# NC.net
KiCad netlist of a schematic drawn in Altium Designer
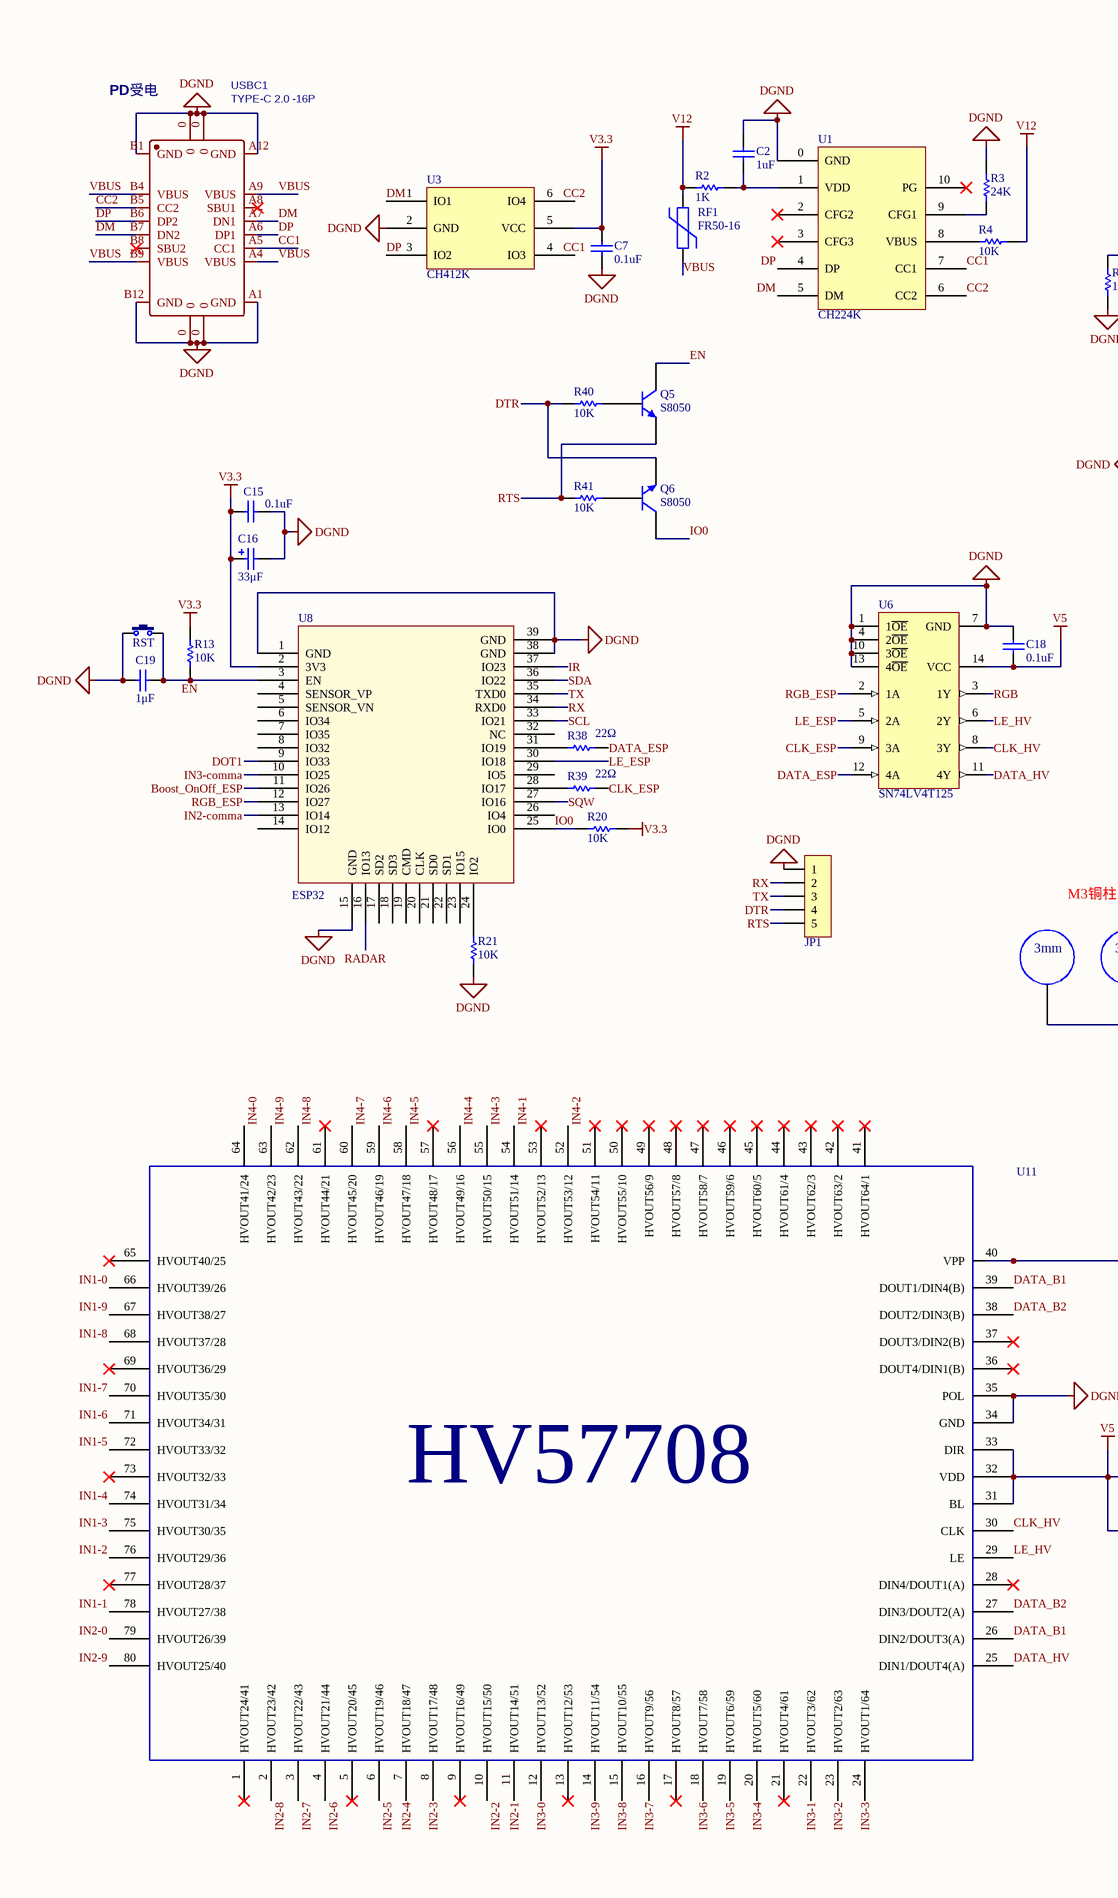
[diagram p0: NC.SchDoc, left]
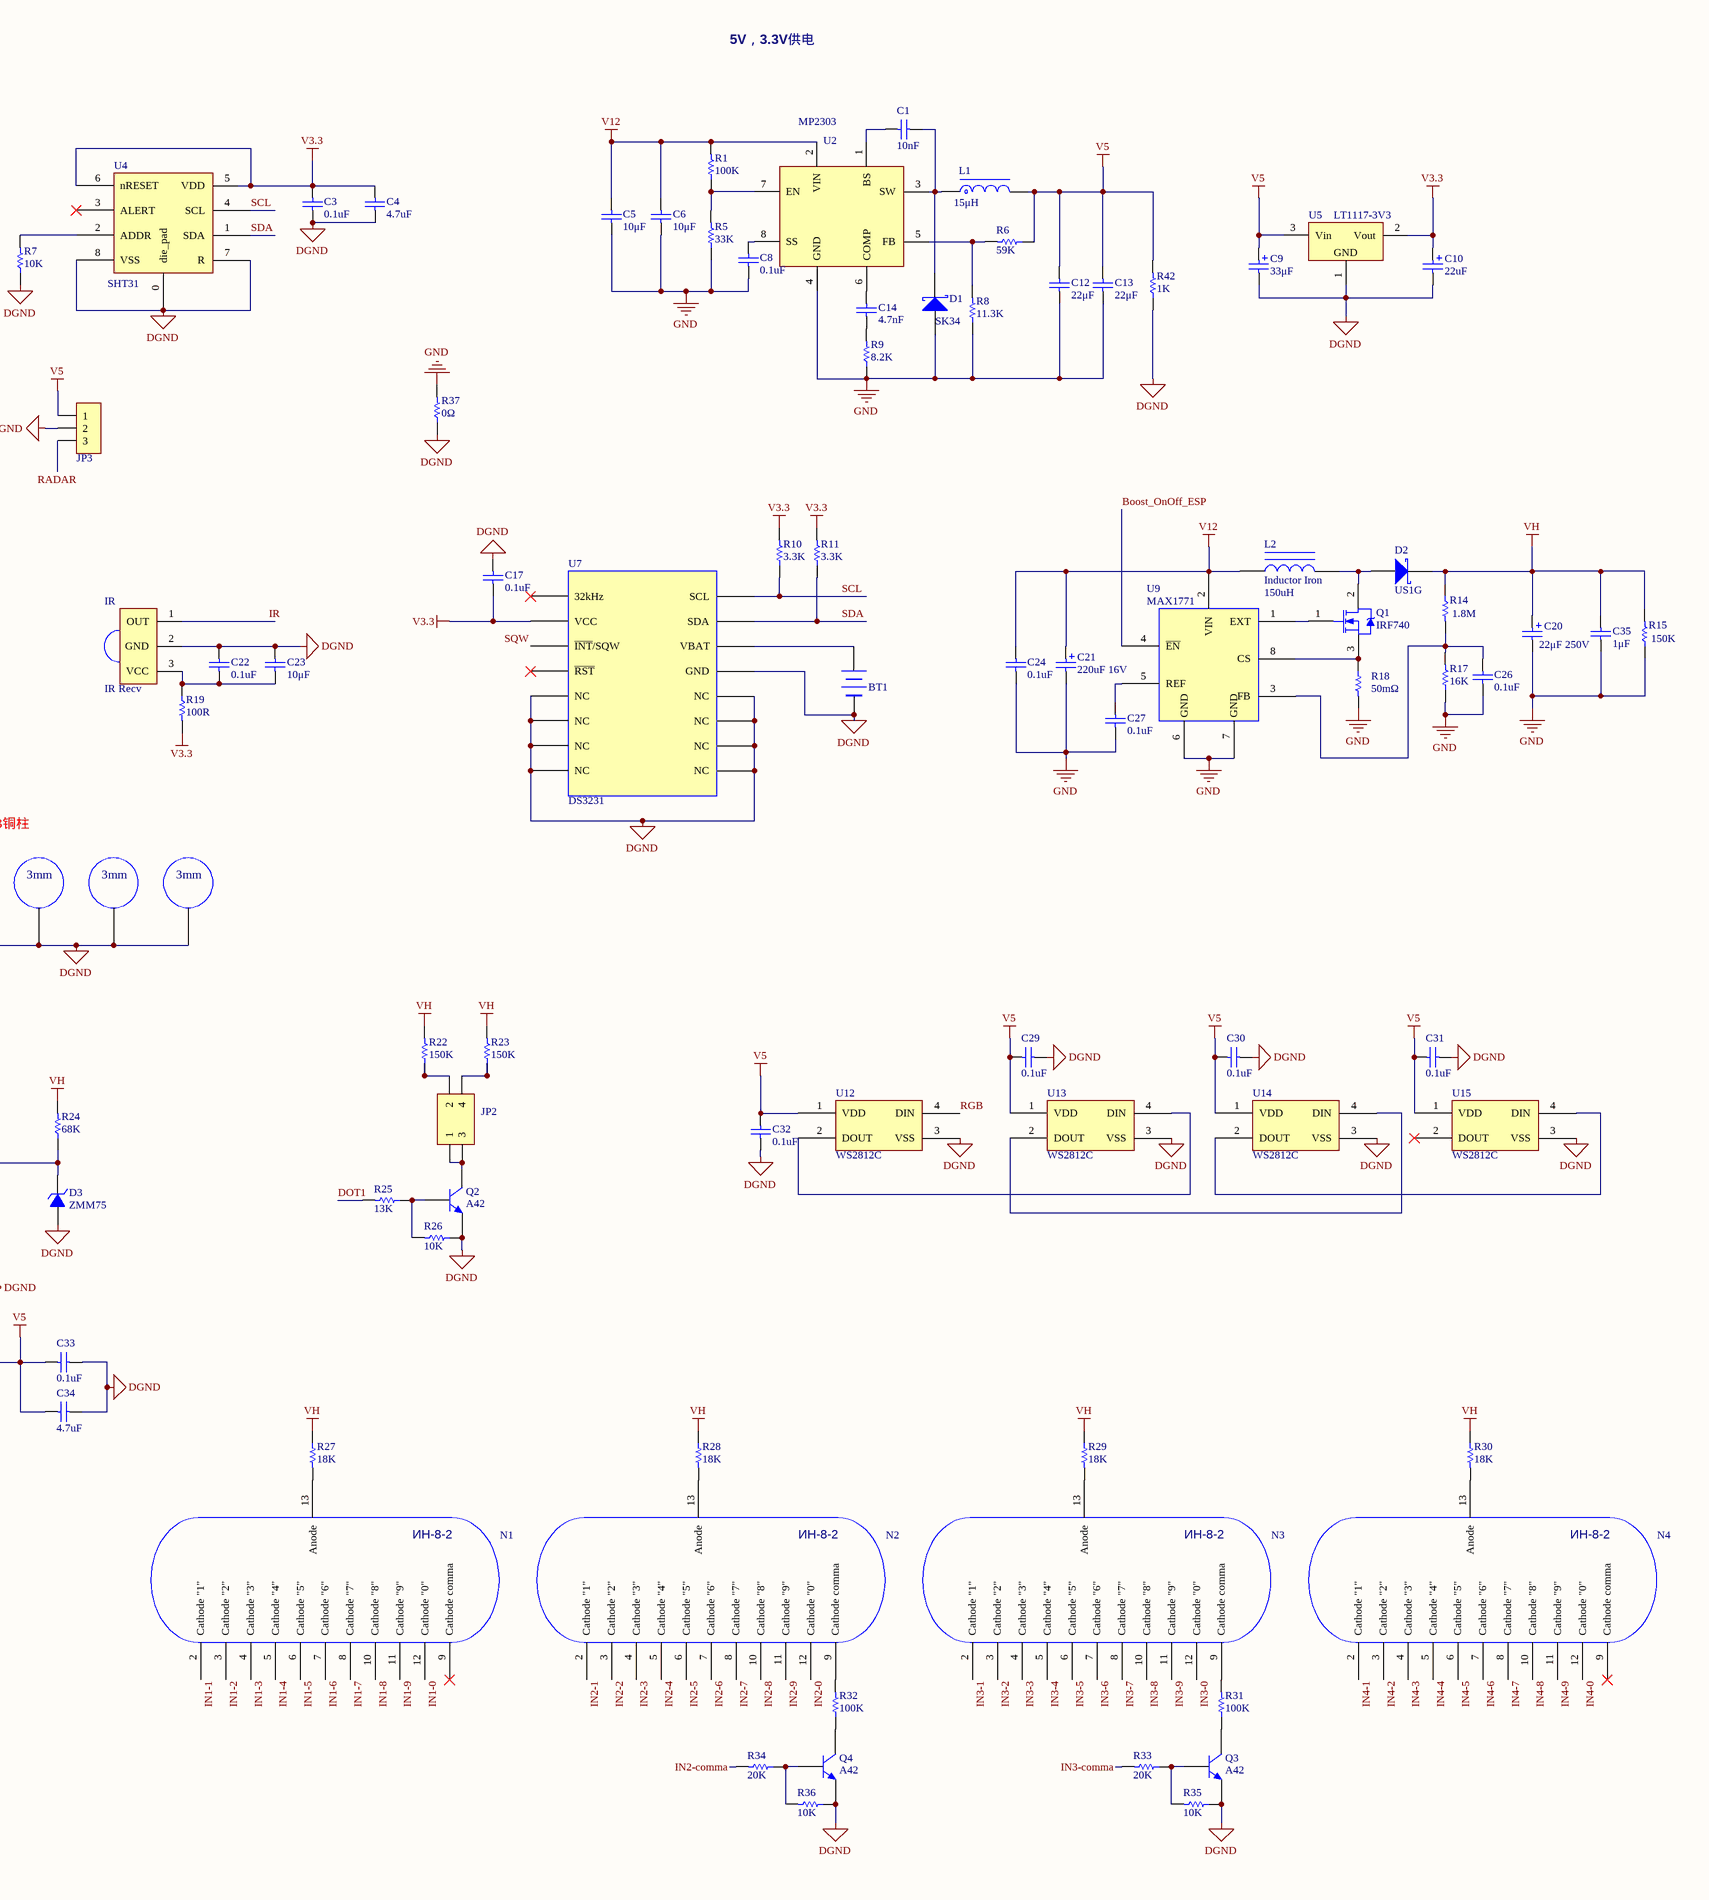
[diagram p1: NC.SchDoc, right]

(export (version "E")
  (design (tool "Eeschema 10.0.6"))
  (components
    (comp (ref "BT1")
      (value "CR1220 holder")
      (footprint "BAT1220")
      (libsource (lib "Schlib1") (part "BATTERY"))
    )
    (comp (ref "C1")
      (value "10nF")
      (footprint "C 0805_L")
      (description "Capacitor")
      (fields (field (name "Comment") "Cap") (field (name "PUBLISHER") "Altium Limited"))
      (libsource (lib "Nixie") (part "Cap"))
    )
    (comp (ref "C2")
      (value "1uF")
      (footprint "C 0805_L")
      (description "Capacitor")
      (fields (field (name "Comment") "Cap") (field (name "PUBLISHER") "Altium Limited"))
      (libsource (lib "Nixie") (part "Cap"))
    )
    (comp (ref "C3")
      (value "0.1uF")
      (footprint "C 0805_L")
      (description "Capacitor")
      (fields (field (name "Comment") "Cap") (field (name "PUBLISHER") "Altium Limited"))
      (libsource (lib "Schlib1") (part "Cap"))
    )
    (comp (ref "C4")
      (value "4.7uF")
      (footprint "C 0805_L")
      (description "Capacitor")
      (fields (field (name "Comment") "Cap") (field (name "PUBLISHER") "Altium Limited"))
      (libsource (lib "Schlib1") (part "Cap"))
    )
    (comp (ref "C5")
      (value "10μF")
      (footprint "C 0805_L")
      (description "Capacitor")
      (fields (field (name "Comment") "Cap") (field (name "PUBLISHER") "Altium Limited"))
      (libsource (lib "Nixie") (part "Cap"))
    )
    (comp (ref "C6")
      (value "10μF")
      (footprint "C 0805_L")
      (description "Capacitor")
      (fields (field (name "Comment") "Cap") (field (name "PUBLISHER") "Altium Limited"))
      (libsource (lib "Nixie") (part "Cap"))
    )
    (comp (ref "C7")
      (value "0.1uF")
      (footprint "C 0805_L")
      (description "Capacitor")
      (fields (field (name "Comment") "Cap") (field (name "PUBLISHER") "Altium Limited"))
      (libsource (lib "Schlib1") (part "Cap"))
    )
    (comp (ref "C8")
      (value "0.1uF")
      (footprint "C 0805_L")
      (description "Capacitor")
      (fields (field (name "Comment") "Cap") (field (name "PUBLISHER") "Altium Limited"))
      (libsource (lib "Nixie") (part "Cap"))
    )
    (comp (ref "C9")
      (value "33μF")
      (footprint "CM C(5*5.4)")
      (description "Polarized Capacitor (Radial)")
      (fields (field (name "Comment") "Cap Pol1") (field (name "PUBLISHER") "Altium Limited"))
      (libsource (lib "Nixie") (part "Cap Pol1"))
    )
    (comp (ref "C10")
      (value "22uF")
      (footprint "CD C(6032)")
      (description "Polarized Capacitor (Radial)")
      (fields (field (name "Comment") "Cap Pol1") (field (name "PUBLISHER") "Altium Limited"))
      (libsource (lib "Nixie") (part "Cap Pol1"))
    )
    (comp (ref "C12")
      (value "22μF")
      (footprint "C 1206_L")
      (description "Capacitor")
      (fields (field (name "Comment") "Cap") (field (name "PUBLISHER") "Altium Limited"))
      (libsource (lib "Nixie") (part "Cap"))
    )
    (comp (ref "C13")
      (value "22μF")
      (footprint "C 1206_L")
      (description "Capacitor")
      (fields (field (name "Comment") "Cap") (field (name "PUBLISHER") "Altium Limited"))
      (libsource (lib "Nixie") (part "Cap"))
    )
    (comp (ref "C14")
      (value "4.7nF")
      (footprint "C 0805_L")
      (description "Capacitor")
      (fields (field (name "Comment") "Cap") (field (name "PUBLISHER") "Altium Limited"))
      (libsource (lib "Nixie") (part "Cap"))
    )
    (comp (ref "C15")
      (value "0.1uF")
      (footprint "C 0805_L")
      (description "Capacitor")
      (fields (field (name "Comment") "Cap") (field (name "PUBLISHER") "Altium Limited"))
      (libsource (lib "Schlib1") (part "Cap"))
    )
    (comp (ref "C16")
      (value "33μF")
      (footprint "CD B(3528)")
      (description "Polarized Capacitor (Radial)")
      (fields (field (name "Comment") "Cap Pol1") (field (name "PUBLISHER") "Altium Limited"))
      (libsource (lib "Nixie") (part "Cap Pol1"))
    )
    (comp (ref "C17")
      (value "0.1uF")
      (footprint "C 0805_L")
      (description "Capacitor")
      (fields (field (name "Comment") "Cap") (field (name "PUBLISHER") "Altium Limited"))
      (libsource (lib "Schlib1") (part "Cap"))
    )
    (comp (ref "C18")
      (value "0.1uF")
      (footprint "C 0805_L")
      (description "Capacitor")
      (fields (field (name "Comment") "Cap") (field (name "PUBLISHER") "Altium Limited"))
      (libsource (lib "Schlib1") (part "Cap"))
    )
    (comp (ref "C19")
      (value "1μF")
      (footprint "C 0805_L")
      (description "Capacitor")
      (fields (field (name "Comment") "Cap") (field (name "PUBLISHER") "Altium Limited"))
      (libsource (lib "Schlib1") (part "Cap"))
    )
    (comp (ref "C20")
      (value "22μF 250V")
      (footprint "CAP 5.0*10*16-H - GD")
      (description "Polarized Capacitor (Radial)")
      (fields (field (name "Comment") "Cap Pol1") (field (name "PUBLISHER") "Altium Limited"))
      (libsource (lib "Nixie") (part "Cap Pol1_3"))
    )
    (comp (ref "C21")
      (value "220uF 16V")
      (footprint "CM D(6.3*7.7)")
      (description "Polarized Capacitor (Radial)")
      (fields
        (field (name "VOLTAGE") "16V")
        (field (name "Comment") "Cap Pol1")
        (field (name "PUBLISHER") "Altium Limited")
      )
      (libsource (lib "Nixie") (part "Cap Pol1_2"))
    )
    (comp (ref "C22")
      (value "0.1uF")
      (footprint "C 0805_L")
      (description "Capacitor")
      (fields (field (name "Comment") "Cap") (field (name "PUBLISHER") "Altium Limited"))
      (libsource (lib "Schlib1") (part "Cap"))
    )
    (comp (ref "C23")
      (value "10μF")
      (footprint "C 0805_L")
      (description "Capacitor")
      (fields (field (name "Comment") "Cap") (field (name "PUBLISHER") "Altium Limited"))
      (libsource (lib "Schlib1") (part "Cap"))
    )
    (comp (ref "C24")
      (value "0.1uF")
      (footprint "C 0805_L")
      (description "Capacitor")
      (fields (field (name "Comment") "Cap") (field (name "PUBLISHER") "Altium Limited"))
      (libsource (lib "Nixie") (part "Cap"))
    )
    (comp (ref "C26")
      (value "0.1uF")
      (footprint "C 0805_L")
      (description "Capacitor")
      (fields (field (name "Comment") "Cap") (field (name "PUBLISHER") "Altium Limited"))
      (libsource (lib "Nixie") (part "Cap"))
    )
    (comp (ref "C27")
      (value "0.1uF")
      (footprint "C 0805_L")
      (description "Capacitor")
      (fields (field (name "Comment") "Cap") (field (name "PUBLISHER") "Altium Limited"))
      (libsource (lib "Schlib1") (part "Cap"))
    )
    (comp (ref "C29")
      (value "0.1uF")
      (footprint "C 0805_L")
      (description "Capacitor")
      (fields (field (name "Comment") "Cap") (field (name "PUBLISHER") "Altium Limited"))
      (libsource (lib "Schlib1") (part "Cap"))
    )
    (comp (ref "C30")
      (value "0.1uF")
      (footprint "C 0805_L")
      (description "Capacitor")
      (fields (field (name "Comment") "Cap") (field (name "PUBLISHER") "Altium Limited"))
      (libsource (lib "Schlib1") (part "Cap"))
    )
    (comp (ref "C31")
      (value "0.1uF")
      (footprint "C 0805_L")
      (description "Capacitor")
      (fields (field (name "Comment") "Cap") (field (name "PUBLISHER") "Altium Limited"))
      (libsource (lib "Schlib1") (part "Cap"))
    )
    (comp (ref "C32")
      (value "0.1uF")
      (footprint "C 0805_L")
      (description "Capacitor")
      (fields (field (name "Comment") "Cap") (field (name "PUBLISHER") "Altium Limited"))
      (libsource (lib "Schlib1") (part "Cap"))
    )
    (comp (ref "C33")
      (value "0.1uF")
      (footprint "C 0805_L")
      (description "Capacitor")
      (fields (field (name "Comment") "Cap") (field (name "PUBLISHER") "Altium Limited"))
      (libsource (lib "Schlib1") (part "Cap"))
    )
    (comp (ref "C34")
      (value "4.7uF")
      (footprint "C 0805_L")
      (description "Capacitor")
      (fields (field (name "Comment") "Cap") (field (name "PUBLISHER") "Altium Limited"))
      (libsource (lib "Schlib1") (part "Cap"))
    )
    (comp (ref "C35")
      (value "1μF")
      (footprint "C 1210_L")
      (description "Capacitor")
      (fields (field (name "Comment") "Cap") (field (name "PUBLISHER") "Altium Limited"))
      (libsource (lib "Nixie") (part "Cap"))
    )
    (comp (ref "D1")
      (value "SK34")
      (footprint "SMA")
      (description "Schottky Diode")
      (fields (field (name "PUBLISHER") "Altium Limited"))
      (libsource (lib "Nixie") (part "D Schottky"))
    )
    (comp (ref "D2")
      (value "US1G")
      (footprint "SMA")
      (description "Schottky Diode")
      (fields (field (name "PUBLISHER") "Altium Limited"))
      (libsource (lib "Nixie") (part "D Schottky"))
    )
    (comp (ref "D3")
      (value "ZMM75")
      (footprint "LL-34")
      (description "75V/0.5W稳压管")
      (fields (field (name "版权归属") "封装库来自淘宝 ID：黄晶宝石"))
      (libsource (lib "Nixie") (part "1N5256"))
    )
    (comp (ref "IR")
      (value "IR Recv")
      (footprint "HDR2.54-LI-3P - duplicate")
      (description "红外接收头")
      (libsource (lib "Nixie") (part "VS1838B"))
    )
    (comp (ref "JP1")
      (value "HDR-1X5")
      (footprint "HDR2.0-LI-5P")
      (description "5P接插件")
      (fields (field (name "版权归属") "封装库来自淘宝 ID：黄晶宝石"))
      (libsource (lib "Nixie") (part "Header 5"))
    )
    (comp (ref "JP2")
      (value "Header2X2")
      (footprint "HDR2.54-LI-2x2P")
      (description "2*2P接插件")
      (fields (field (name "版权归属") "封装库来自淘宝 ID：黄晶宝石"))
      (libsource (lib "Nixie") (part "Header 2X2"))
    )
    (comp (ref "JP3")
      (value "HDR-1X3")
      (footprint "ZH1.5-WS-3P")
      (description "3P接插件")
      (fields (field (name "版权归属") "封装库来自淘宝 ID：黄晶宝石"))
      (libsource (lib "Nixie") (part "Header 3"))
    )
    (comp (ref "L1")
      (value "15μH")
      (footprint "CKST0603")
      (description "CD系列贴片线绕功率电感")
      (fields (field (name "Comment") "10uH"))
      (libsource (lib "0.1 - 电阻-电容-电感") (part "L-SMD"))
    )
    (comp (ref "L2")
      (value "Inductor Iron")
      (footprint "CD104")
      (description "Magnetic-Core Inductor")
      (fields (field (name "ALTIUM_VALUE") "150uH") (field (name "PUBLISHER") "Altium Limited"))
      (libsource (lib "Nixie") (part "Inductor Iron"))
    )
    (comp (ref "N1") (value "ИН-8-2") (footprint "IN8-2") (libsource (lib "Nixie") (part "ИН-8-2")))
    (comp (ref "N2") (value "ИН-8-2") (footprint "IN8-2") (libsource (lib "Nixie") (part "ИН-8-2")))
    (comp (ref "N3") (value "ИН-8-2") (footprint "IN8-2") (libsource (lib "Nixie") (part "ИН-8-2")))
    (comp (ref "N4") (value "ИН-8-2") (footprint "IN8-2") (libsource (lib "Nixie") (part "ИН-8-2")))
    (comp (ref "Q1")
      (value "IRF740")
      (footprint "TO-263-2L")
      (description "N-Channel Power MOSFET")
      (fields (field (name "PUBLISHER") "Altium Limited"))
      (libsource (lib "Nixie") (part "NMOS-2"))
    )
    (comp (ref "Q2")
      (value "A42")
      (footprint "SOT-23-3L")
      (description "NPN Bipolar Transistor")
      (fields (field (name "PUBLISHER") "Altium Limited"))
      (libsource (lib "Schlib1") (part "NPN"))
    )
    (comp (ref "Q3")
      (value "A42")
      (footprint "SOT-23-3L")
      (description "NPN Bipolar Transistor")
      (fields (field (name "PUBLISHER") "Altium Limited"))
      (libsource (lib "Schlib1") (part "NPN"))
    )
    (comp (ref "Q4")
      (value "A42")
      (footprint "SOT-23-3L")
      (description "NPN Bipolar Transistor")
      (fields (field (name "PUBLISHER") "Altium Limited"))
      (libsource (lib "Schlib1") (part "NPN"))
    )
    (comp (ref "Q5")
      (value "S8050")
      (footprint "SOT-23-3L")
      (description "NPN Bipolar Transistor")
      (fields (field (name "PUBLISHER") "Altium Limited"))
      (libsource (lib "Schlib1") (part "NPN"))
    )
    (comp (ref "Q6")
      (value "S8050")
      (footprint "SOT-23-3L")
      (description "NPN Bipolar Transistor")
      (fields (field (name "PUBLISHER") "Altium Limited"))
      (libsource (lib "Schlib1") (part "NPN"))
    )
    (comp (ref "R1")
      (value "100K")
      (footprint "R 0805_L")
      (description "Resistor")
      (fields (field (name "PUBLISHER") "Altium Limited"))
      (libsource (lib "Nixie") (part "Resistor"))
    )
    (comp (ref "R2")
      (value "1K")
      (footprint "R 0805_L")
      (description "Resistor")
      (fields (field (name "PUBLISHER") "Altium Limited"))
      (libsource (lib "Nixie") (part "Resistor"))
    )
    (comp (ref "R3")
      (value "24K")
      (footprint "R 0805_L")
      (description "Resistor")
      (fields (field (name "PUBLISHER") "Altium Limited"))
      (libsource (lib "Nixie") (part "Resistor"))
    )
    (comp (ref "R4")
      (value "10K")
      (footprint "R 0805_L")
      (description "Resistor")
      (fields (field (name "PUBLISHER") "Altium Limited"))
      (libsource (lib "Nixie") (part "Resistor"))
    )
    (comp (ref "R5")
      (value "33K")
      (footprint "R 0805_L")
      (description "Resistor")
      (fields (field (name "PUBLISHER") "Altium Limited"))
      (libsource (lib "Nixie") (part "Resistor"))
    )
    (comp (ref "R6")
      (value "59K")
      (footprint "R 0805_L")
      (description "Resistor")
      (fields (field (name "PUBLISHER") "Altium Limited"))
      (libsource (lib "Nixie") (part "Resistor"))
    )
    (comp (ref "R7")
      (value "10K")
      (footprint "R 0805_L")
      (description "Resistor")
      (fields (field (name "PUBLISHER") "Altium Limited"))
      (libsource (lib "Nixie") (part "Resistor"))
    )
    (comp (ref "R8")
      (value "11.3K")
      (footprint "R 0805_L")
      (description "Resistor")
      (fields (field (name "PUBLISHER") "Altium Limited"))
      (libsource (lib "Nixie") (part "Resistor"))
    )
    (comp (ref "R9")
      (value "8.2K")
      (footprint "R 0805_L")
      (description "Resistor")
      (fields (field (name "PUBLISHER") "Altium Limited"))
      (libsource (lib "Nixie") (part "Resistor"))
    )
    (comp (ref "R10")
      (value "3.3K")
      (footprint "R 0805_L")
      (description "Resistor")
      (fields (field (name "PUBLISHER") "Altium Limited"))
      (libsource (lib "Nixie") (part "Resistor"))
    )
    (comp (ref "R11")
      (value "3.3K")
      (footprint "R 0805_L")
      (description "Resistor")
      (fields (field (name "PUBLISHER") "Altium Limited"))
      (libsource (lib "Nixie") (part "Resistor"))
    )
    (comp (ref "R13")
      (value "10K")
      (footprint "R 0805_L")
      (description "Resistor")
      (fields (field (name "PUBLISHER") "Altium Limited"))
      (libsource (lib "Nixie") (part "Resistor"))
    )
    (comp (ref "R14")
      (value "1.8M")
      (footprint "R 0805_L")
      (description "Semiconductor Resistor")
      (fields (field (name "Comment") "Res Semi") (field (name "PUBLISHER") "Altium Limited"))
      (libsource (lib "Nixie") (part "Res Semi"))
    )
    (comp (ref "R15")
      (value "150K")
      (footprint "R 1206_L")
      (description "Resistor")
      (fields (field (name "PUBLISHER") "Altium Limited"))
      (libsource (lib "Nixie") (part "Resistor"))
    )
    (comp (ref "R17")
      (value "16K")
      (footprint "R 0805_L")
      (description "Resistor")
      (fields (field (name "PUBLISHER") "Altium Limited"))
      (libsource (lib "Nixie") (part "Resistor"))
    )
    (comp (ref "R18")
      (value "50mΩ")
      (footprint "R 1206_L")
      (description "Semiconductor Resistor")
      (fields (field (name "Comment") "Res Semi") (field (name "PUBLISHER") "Altium Limited"))
      (libsource (lib "Nixie") (part "Res Semi"))
    )
    (comp (ref "R19")
      (value "100R")
      (footprint "R 0805_L")
      (description "Resistor")
      (fields (field (name "PUBLISHER") "Altium Limited"))
      (libsource (lib "Nixie") (part "Resistor"))
    )
    (comp (ref "R20")
      (value "10K")
      (footprint "R 0805_L")
      (description "Resistor")
      (fields (field (name "PUBLISHER") "Altium Limited"))
      (libsource (lib "Nixie") (part "Resistor"))
    )
    (comp (ref "R21")
      (value "10K")
      (footprint "R 0805_L")
      (description "Resistor")
      (fields (field (name "PUBLISHER") "Altium Limited"))
      (libsource (lib "Nixie") (part "Resistor"))
    )
    (comp (ref "R22")
      (value "150K")
      (footprint "R 0805_L")
      (description "Resistor")
      (fields (field (name "PUBLISHER") "Altium Limited"))
      (libsource (lib "Nixie") (part "Resistor"))
    )
    (comp (ref "R23")
      (value "150K")
      (footprint "R 0805_L")
      (description "Resistor")
      (fields (field (name "PUBLISHER") "Altium Limited"))
      (libsource (lib "Nixie") (part "Resistor"))
    )
    (comp (ref "R24")
      (value "68K")
      (footprint "R 1206_L")
      (description "Resistor")
      (fields (field (name "PUBLISHER") "Altium Limited"))
      (libsource (lib "Nixie") (part "Resistor"))
    )
    (comp (ref "R25")
      (value "13K")
      (footprint "R 0805_L")
      (description "Resistor")
      (fields (field (name "PUBLISHER") "Altium Limited"))
      (libsource (lib "Nixie") (part "Resistor"))
    )
    (comp (ref "R26")
      (value "10K")
      (footprint "R 0805_L")
      (description "Resistor")
      (fields (field (name "PUBLISHER") "Altium Limited"))
      (libsource (lib "Nixie") (part "Resistor"))
    )
    (comp (ref "R27")
      (value "18K")
      (footprint "R 0805_L")
      (description "Resistor")
      (fields (field (name "PUBLISHER") "Altium Limited"))
      (libsource (lib "Nixie") (part "Resistor"))
    )
    (comp (ref "R28")
      (value "18K")
      (footprint "R 0805_L")
      (description "Resistor")
      (fields (field (name "PUBLISHER") "Altium Limited"))
      (libsource (lib "Nixie") (part "Resistor"))
    )
    (comp (ref "R29")
      (value "18K")
      (footprint "R 0805_L")
      (description "Resistor")
      (fields (field (name "PUBLISHER") "Altium Limited"))
      (libsource (lib "Nixie") (part "Resistor"))
    )
    (comp (ref "R30")
      (value "18K")
      (footprint "R 0805_L")
      (description "Resistor")
      (fields (field (name "PUBLISHER") "Altium Limited"))
      (libsource (lib "Nixie") (part "Resistor"))
    )
    (comp (ref "R31")
      (value "100K")
      (footprint "R 0805_L")
      (description "Resistor")
      (fields (field (name "PUBLISHER") "Altium Limited"))
      (libsource (lib "Nixie") (part "Resistor"))
    )
    (comp (ref "R32")
      (value "100K")
      (footprint "R 0805_L")
      (description "Resistor")
      (fields (field (name "PUBLISHER") "Altium Limited"))
      (libsource (lib "Nixie") (part "Resistor"))
    )
    (comp (ref "R33")
      (value "20K")
      (footprint "R 0805_L")
      (description "Resistor")
      (fields (field (name "PUBLISHER") "Altium Limited"))
      (libsource (lib "Nixie") (part "Resistor"))
    )
    (comp (ref "R34")
      (value "20K")
      (footprint "R 0805_L")
      (description "Resistor")
      (fields (field (name "PUBLISHER") "Altium Limited"))
      (libsource (lib "Nixie") (part "Resistor"))
    )
    (comp (ref "R35")
      (value "10K")
      (footprint "R 0805_L")
      (description "Resistor")
      (fields (field (name "PUBLISHER") "Altium Limited"))
      (libsource (lib "Nixie") (part "Resistor"))
    )
    (comp (ref "R36")
      (value "10K")
      (footprint "R 0805_L")
      (description "Resistor")
      (fields (field (name "PUBLISHER") "Altium Limited"))
      (libsource (lib "Nixie") (part "Resistor"))
    )
    (comp (ref "R37")
      (value "0Ω")
      (footprint "R 0805_L")
      (description "Resistor")
      (fields (field (name "PUBLISHER") "Altium Limited"))
      (libsource (lib "Nixie") (part "Resistor"))
    )
    (comp (ref "R38")
      (value "22Ω")
      (footprint "R 0805_L")
      (description "Resistor")
      (fields (field (name "PUBLISHER") "Altium Limited"))
      (libsource (lib "Nixie") (part "Resistor"))
    )
    (comp (ref "R39")
      (value "22Ω")
      (footprint "R 0805_L")
      (description "Resistor")
      (fields (field (name "PUBLISHER") "Altium Limited"))
      (libsource (lib "Nixie") (part "Resistor"))
    )
    (comp (ref "R40")
      (value "10K")
      (footprint "R 0805_L")
      (description "Resistor")
      (fields (field (name "PUBLISHER") "Altium Limited"))
      (libsource (lib "Nixie") (part "Resistor"))
    )
    (comp (ref "R41")
      (value "10K")
      (footprint "R 0805_L")
      (description "Resistor")
      (fields (field (name "PUBLISHER") "Altium Limited"))
      (libsource (lib "Nixie") (part "Resistor"))
    )
    (comp (ref "R42")
      (value "1K")
      (footprint "R 0805_L")
      (description "Resistor")
      (fields (field (name "PUBLISHER") "Altium Limited"))
      (libsource (lib "Nixie") (part "Resistor"))
    )
    (comp (ref "RF1")
      (value "FR50-16")
      (footprint "FU 1206")
      (description "PPTC自恢复保险丝")
      (libsource (lib "Nixie") (part "PPTC"))
    )
    (comp (ref "RST")
      (value "3x6x5")
      (footprint "TSW SMD-3*6*2.5")
      (description "3x6轻触开关")
      (fields (field (name "版权归属") "封装库来自淘宝 ID：黄晶宝石"))
      (libsource (lib "Nixie") (part "TSW 3x6"))
    )
    (comp (ref "T1") (value "铜柱") (footprint "螺丝孔-3mm") (libsource (lib "Nixie") (part "铜柱")))
    (comp (ref "T2") (value "铜柱") (footprint "螺丝孔-3mm") (libsource (lib "Nixie") (part "铜柱")))
    (comp (ref "T3") (value "铜柱") (footprint "螺丝孔-3mm") (libsource (lib "Nixie") (part "铜柱")))
    (comp (ref "T4") (value "铜柱") (footprint "螺丝孔-3mm") (libsource (lib "Nixie") (part "铜柱")))
    (comp (ref "U1")
      (value "CH224K")
      (footprint "ESSOP10")
      (description "PD协议受电芯片")
      (libsource (lib "Nixie") (part "CH224K"))
    )
    (comp (ref "U2")
      (value "MP2303")
      (footprint "SOIC8E")
      (description "DC-DC降压芯片。4.75V-28V，3A")
      (libsource (lib "Nixie") (part "MP2303"))
    )
    (comp (ref "U3")
      (value "CH412K")
      (footprint "SOT-363")
      (description "四路ESD保护")
      (libsource (lib "Nixie") (part "CH412K"))
    )
    (comp (ref "U4")
      (value "SHT31")
      (footprint "DFN-8")
      (description "Humidity and Temperature Sensor")
      (libsource (lib "Schlib1") (part "SHT3x"))
    )
    (comp (ref "U5")
      (value "LT1117-3V3")
      (footprint "SOT223_L")
      (description "三端稳压芯片")
      (fields (field (name "版权归属") "源创客"))
      (libsource (lib "Nixie") (part "AMS1117"))
    )
    (comp (ref "U6")
      (value "SN74LV4T125")
      (footprint "TSSOP14_L")
      (description "单电源4路逻辑电平转换")
      (libsource (lib "Nixie") (part "SN74LV4T125"))
    )
    (comp (ref "U7") (value "DS3231") (footprint "SOP16_75MM") (libsource (lib "Schlib1") (part "DS3231")))
    (comp (ref "U8") (value "ESP32") (footprint "ESP32") (libsource (lib "Schlib1") (part "ESP32")))
    (comp (ref "U9") (value "MAX1771") (footprint "SOIC8") (libsource (lib "Nixie") (part "MAX1771")))
    (comp (ref "U11") (value "HV57708") (footprint "HV57708PG") (libsource (lib "Schlib1") (part "HV57708")))
    (comp (ref "U12")
      (value "WS2812C")
      (footprint "WS2812")
      (description "RGB发光管")
      (libsource (lib "Schlib1") (part "WS2812"))
    )
    (comp (ref "U13")
      (value "WS2812C")
      (footprint "WS2812")
      (description "RGB发光管")
      (libsource (lib "Schlib1") (part "WS2812"))
    )
    (comp (ref "U14")
      (value "WS2812C")
      (footprint "WS2812")
      (description "RGB发光管")
      (libsource (lib "Schlib1") (part "WS2812"))
    )
    (comp (ref "U15")
      (value "WS2812C")
      (footprint "WS2812")
      (description "RGB发光管")
      (libsource (lib "Schlib1") (part "WS2812"))
    )
    (comp (ref "USBC1")
      (value "TYPE-C 2.0 -16P")
      (footprint "USB-C-SMD_TYPE-C-USB-5")
      (description "USB2.0 Type-C 母座 16Pin")
      (libsource (lib "Nixie") (part "USB2.0 Type-C 16Pin母座"))
    )
  )
  (nets
    (net (code "1") (name "/Boost_OnOff_ESP") (class "Default")
      (node (ref "U8") (pin "11") (pinfunction "IO26_11") (pintype "passive"))
      (node (ref "U9") (pin "4") (pinfunction "~{EN}_4") (pintype "passive"))
    )
    (net (code "2") (name "/CC1") (class "Default")
      (node (ref "U1") (pin "7") (pinfunction "CC1_7") (pintype "passive"))
      (node (ref "U3") (pin "4") (pinfunction "IO3_4") (pintype "passive"))
      (node (ref "USBC1") (pin "A5") (pinfunction "CC1_A5") (pintype "passive"))
    )
    (net (code "3") (name "/CC2") (class "Default")
      (node (ref "U1") (pin "6") (pinfunction "CC2_6") (pintype "passive"))
      (node (ref "U3") (pin "6") (pinfunction "IO4_6") (pintype "passive"))
      (node (ref "USBC1") (pin "B5") (pinfunction "CC2_B5") (pintype "passive"))
    )
    (net (code "4") (name "/CLK_ESP") (class "Default")
      (node (ref "R39") (pin "1") (pinfunction "1_1") (pintype "passive"))
      (node (ref "U6") (pin "9") (pinfunction "3A_9") (pintype "input"))
    )
    (net (code "5") (name "/CLK_HV") (class "Default")
      (node (ref "U11") (pin "30") (pinfunction "CLK_30") (pintype "passive"))
      (node (ref "U6") (pin "8") (pinfunction "3Y_8") (pintype "output"))
    )
    (net (code "6") (name "/DATA_B1") (class "Default")
      (node (ref "U11") (pin "26") (pinfunction "DIN2/DOUT3(A)_26") (pintype "passive"))
      (node (ref "U11") (pin "39") (pinfunction "DOUT1/DIN4(B)_39") (pintype "passive"))
    )
    (net (code "7") (name "/DATA_B2") (class "Default")
      (node (ref "U11") (pin "27") (pinfunction "DIN3/DOUT2(A)_27") (pintype "passive"))
      (node (ref "U11") (pin "38") (pinfunction "DOUT2/DIN3(B)_38") (pintype "passive"))
    )
    (net (code "8") (name "/DATA_ESP") (class "Default")
      (node (ref "R38") (pin "1") (pinfunction "1_1") (pintype "passive"))
      (node (ref "U6") (pin "12") (pinfunction "4A_12") (pintype "input"))
    )
    (net (code "9") (name "/DATA_HV") (class "Default")
      (node (ref "U11") (pin "25") (pinfunction "DIN1/DOUT4(A)_25") (pintype "passive"))
      (node (ref "U6") (pin "11") (pinfunction "4Y_11") (pintype "output"))
    )
    (net (code "10") (name "/DM") (class "Default")
      (node (ref "U1") (pin "5") (pinfunction "DM_5") (pintype "passive"))
      (node (ref "U3") (pin "1") (pinfunction "IO1_1") (pintype "passive"))
      (node (ref "USBC1") (pin "A7") (pinfunction "DN1_A7") (pintype "passive"))
      (node (ref "USBC1") (pin "B7") (pinfunction "DN2_B7") (pintype "passive"))
    )
    (net (code "11") (name "/DOT1") (class "Default")
      (node (ref "R25") (pin "2") (pinfunction "2_2") (pintype "passive"))
      (node (ref "U8") (pin "9") (pinfunction "IO33_9") (pintype "passive"))
    )
    (net (code "12") (name "/DP") (class "Default")
      (node (ref "U1") (pin "4") (pinfunction "DP_4") (pintype "passive"))
      (node (ref "U3") (pin "3") (pinfunction "IO2_3") (pintype "passive"))
      (node (ref "USBC1") (pin "A6") (pinfunction "DP1_A6") (pintype "passive"))
      (node (ref "USBC1") (pin "B6") (pinfunction "DP2_B6") (pintype "passive"))
    )
    (net (code "13") (name "/DTR") (class "Default")
      (node (ref "JP1") (pin "4") (pinfunction "4_4") (pintype "passive"))
      (node (ref "Q6") (pin "2") (pinfunction "E_2") (pintype "passive"))
      (node (ref "R40") (pin "2") (pinfunction "2_2") (pintype "passive"))
    )
    (net (code "14") (name "/EN") (class "Default")
      (node (ref "C19") (pin "2") (pinfunction "2_2") (pintype "passive"))
      (node (ref "Q5") (pin "3") (pinfunction "C_3") (pintype "passive"))
      (node (ref "R13") (pin "1") (pinfunction "1_1") (pintype "passive"))
      (node (ref "RST") (pin "2") (pinfunction "2_2") (pintype "passive"))
      (node (ref "U8") (pin "3") (pinfunction "EN_3") (pintype "passive"))
    )
    (net (code "15") (name "/IN1-0") (class "Default")
      (node (ref "N1") (pin "12") (pinfunction "Cathode_\"0\"_12") (pintype "passive"))
      (node (ref "U11") (pin "66") (pinfunction "HVOUT39/26_66") (pintype "passive"))
    )
    (net (code "16") (name "/IN1-1") (class "Default")
      (node (ref "N1") (pin "2") (pinfunction "Cathode_\"1\"_2") (pintype "passive"))
      (node (ref "U11") (pin "78") (pinfunction "HVOUT27/38_78") (pintype "passive"))
    )
    (net (code "17") (name "/IN1-2") (class "Default")
      (node (ref "N1") (pin "3") (pinfunction "Cathode_\"2\"_3") (pintype "passive"))
      (node (ref "U11") (pin "76") (pinfunction "HVOUT29/36_76") (pintype "passive"))
    )
    (net (code "18") (name "/IN1-3") (class "Default")
      (node (ref "N1") (pin "4") (pinfunction "Cathode_\"3\"_4") (pintype "passive"))
      (node (ref "U11") (pin "75") (pinfunction "HVOUT30/35_75") (pintype "passive"))
    )
    (net (code "19") (name "/IN1-4") (class "Default")
      (node (ref "N1") (pin "5") (pinfunction "Cathode_\"4\"_5") (pintype "passive"))
      (node (ref "U11") (pin "74") (pinfunction "HVOUT31/34_74") (pintype "passive"))
    )
    (net (code "20") (name "/IN1-5") (class "Default")
      (node (ref "N1") (pin "6") (pinfunction "Cathode_\"5\"_6") (pintype "passive"))
      (node (ref "U11") (pin "72") (pinfunction "HVOUT33/32_72") (pintype "passive"))
    )
    (net (code "21") (name "/IN1-6") (class "Default")
      (node (ref "N1") (pin "7") (pinfunction "Cathode_\"6\"_7") (pintype "passive"))
      (node (ref "U11") (pin "71") (pinfunction "HVOUT34/31_71") (pintype "passive"))
    )
    (net (code "22") (name "/IN1-7") (class "Default")
      (node (ref "N1") (pin "8") (pinfunction "Cathode_\"7\"_8") (pintype "passive"))
      (node (ref "U11") (pin "70") (pinfunction "HVOUT35/30_70") (pintype "passive"))
    )
    (net (code "23") (name "/IN1-8") (class "Default")
      (node (ref "N1") (pin "10") (pinfunction "Cathode_\"8\"_10") (pintype "passive"))
      (node (ref "U11") (pin "68") (pinfunction "HVOUT37/28_68") (pintype "passive"))
    )
    (net (code "24") (name "/IN1-9") (class "Default")
      (node (ref "N1") (pin "11") (pinfunction "Cathode_\"9\"_11") (pintype "passive"))
      (node (ref "U11") (pin "67") (pinfunction "HVOUT38/27_67") (pintype "passive"))
    )
    (net (code "25") (name "/IN2-0") (class "Default")
      (node (ref "N2") (pin "12") (pinfunction "Cathode_\"0\"_12") (pintype "passive"))
      (node (ref "U11") (pin "79") (pinfunction "HVOUT26/39_79") (pintype "passive"))
    )
    (net (code "26") (name "/IN2-1") (class "Default")
      (node (ref "N2") (pin "2") (pinfunction "Cathode_\"1\"_2") (pintype "passive"))
      (node (ref "U11") (pin "11") (pinfunction "HVOUT14/51_11") (pintype "passive"))
    )
    (net (code "27") (name "/IN2-2") (class "Default")
      (node (ref "N2") (pin "3") (pinfunction "Cathode_\"2\"_3") (pintype "passive"))
      (node (ref "U11") (pin "10") (pinfunction "HVOUT15/50_10") (pintype "passive"))
    )
    (net (code "28") (name "/IN2-3") (class "Default")
      (node (ref "N2") (pin "4") (pinfunction "Cathode_\"3\"_4") (pintype "passive"))
      (node (ref "U11") (pin "8") (pinfunction "HVOUT17/48_8") (pintype "passive"))
    )
    (net (code "29") (name "/IN2-4") (class "Default")
      (node (ref "N2") (pin "5") (pinfunction "Cathode_\"4\"_5") (pintype "passive"))
      (node (ref "U11") (pin "7") (pinfunction "HVOUT18/47_7") (pintype "passive"))
    )
    (net (code "30") (name "/IN2-5") (class "Default")
      (node (ref "N2") (pin "6") (pinfunction "Cathode_\"5\"_6") (pintype "passive"))
      (node (ref "U11") (pin "6") (pinfunction "HVOUT19/46_6") (pintype "passive"))
    )
    (net (code "31") (name "/IN2-6") (class "Default")
      (node (ref "N2") (pin "7") (pinfunction "Cathode_\"6\"_7") (pintype "passive"))
      (node (ref "U11") (pin "4") (pinfunction "HVOUT21/44_4") (pintype "passive"))
    )
    (net (code "32") (name "/IN2-7") (class "Default")
      (node (ref "N2") (pin "8") (pinfunction "Cathode_\"7\"_8") (pintype "passive"))
      (node (ref "U11") (pin "3") (pinfunction "HVOUT22/43_3") (pintype "passive"))
    )
    (net (code "33") (name "/IN2-8") (class "Default")
      (node (ref "N2") (pin "10") (pinfunction "Cathode_\"8\"_10") (pintype "passive"))
      (node (ref "U11") (pin "2") (pinfunction "HVOUT23/42_2") (pintype "passive"))
    )
    (net (code "34") (name "/IN2-9") (class "Default")
      (node (ref "N2") (pin "11") (pinfunction "Cathode_\"9\"_11") (pintype "passive"))
      (node (ref "U11") (pin "80") (pinfunction "HVOUT25/40_80") (pintype "passive"))
    )
    (net (code "35") (name "/IN2-comma") (class "Default")
      (node (ref "R34") (pin "2") (pinfunction "2_2") (pintype "passive"))
      (node (ref "U8") (pin "13") (pinfunction "IO14_13") (pintype "passive"))
    )
    (net (code "36") (name "/IN3-0") (class "Default")
      (node (ref "N3") (pin "12") (pinfunction "Cathode_\"0\"_12") (pintype "passive"))
      (node (ref "U11") (pin "12") (pinfunction "HVOUT13/52_12") (pintype "passive"))
    )
    (net (code "37") (name "/IN3-1") (class "Default")
      (node (ref "N3") (pin "2") (pinfunction "Cathode_\"1\"_2") (pintype "passive"))
      (node (ref "U11") (pin "22") (pinfunction "HVOUT3/62_22") (pintype "passive"))
    )
    (net (code "38") (name "/IN3-2") (class "Default")
      (node (ref "N3") (pin "3") (pinfunction "Cathode_\"2\"_3") (pintype "passive"))
      (node (ref "U11") (pin "23") (pinfunction "HVOUT2/63_23") (pintype "passive"))
    )
    (net (code "39") (name "/IN3-3") (class "Default")
      (node (ref "N3") (pin "4") (pinfunction "Cathode_\"3\"_4") (pintype "passive"))
      (node (ref "U11") (pin "24") (pinfunction "HVOUT1/64_24") (pintype "passive"))
    )
    (net (code "40") (name "/IN3-4") (class "Default")
      (node (ref "N3") (pin "5") (pinfunction "Cathode_\"4\"_5") (pintype "passive"))
      (node (ref "U11") (pin "20") (pinfunction "HVOUT5/60_20") (pintype "passive"))
    )
    (net (code "41") (name "/IN3-5") (class "Default")
      (node (ref "N3") (pin "6") (pinfunction "Cathode_\"5\"_6") (pintype "passive"))
      (node (ref "U11") (pin "19") (pinfunction "HVOUT6/59_19") (pintype "passive"))
    )
    (net (code "42") (name "/IN3-6") (class "Default")
      (node (ref "N3") (pin "7") (pinfunction "Cathode_\"6\"_7") (pintype "passive"))
      (node (ref "U11") (pin "18") (pinfunction "HVOUT7/58_18") (pintype "passive"))
    )
    (net (code "43") (name "/IN3-7") (class "Default")
      (node (ref "N3") (pin "8") (pinfunction "Cathode_\"7\"_8") (pintype "passive"))
      (node (ref "U11") (pin "16") (pinfunction "HVOUT9/56_16") (pintype "passive"))
    )
    (net (code "44") (name "/IN3-8") (class "Default")
      (node (ref "N3") (pin "10") (pinfunction "Cathode_\"8\"_10") (pintype "passive"))
      (node (ref "U11") (pin "15") (pinfunction "HVOUT10/55_15") (pintype "passive"))
    )
    (net (code "45") (name "/IN3-9") (class "Default")
      (node (ref "N3") (pin "11") (pinfunction "Cathode_\"9\"_11") (pintype "passive"))
      (node (ref "U11") (pin "14") (pinfunction "HVOUT11/54_14") (pintype "passive"))
    )
    (net (code "46") (name "/IN3-comma") (class "Default")
      (node (ref "R33") (pin "2") (pinfunction "2_2") (pintype "passive"))
      (node (ref "U8") (pin "10") (pinfunction "IO25_10") (pintype "passive"))
    )
    (net (code "47") (name "/IN4-0") (class "Default")
      (node (ref "N4") (pin "12") (pinfunction "Cathode_\"0\"_12") (pintype "passive"))
      (node (ref "U11") (pin "64") (pinfunction "HVOUT41/24_64") (pintype "passive"))
    )
    (net (code "48") (name "/IN4-1") (class "Default")
      (node (ref "N4") (pin "2") (pinfunction "Cathode_\"1\"_2") (pintype "passive"))
      (node (ref "U11") (pin "54") (pinfunction "HVOUT51/14_54") (pintype "passive"))
    )
    (net (code "49") (name "/IN4-2") (class "Default")
      (node (ref "N4") (pin "3") (pinfunction "Cathode_\"2\"_3") (pintype "passive"))
      (node (ref "U11") (pin "52") (pinfunction "HVOUT53/12_52") (pintype "passive"))
    )
    (net (code "50") (name "/IN4-3") (class "Default")
      (node (ref "N4") (pin "4") (pinfunction "Cathode_\"3\"_4") (pintype "passive"))
      (node (ref "U11") (pin "55") (pinfunction "HVOUT50/15_55") (pintype "passive"))
    )
    (net (code "51") (name "/IN4-4") (class "Default")
      (node (ref "N4") (pin "5") (pinfunction "Cathode_\"4\"_5") (pintype "passive"))
      (node (ref "U11") (pin "56") (pinfunction "HVOUT49/16_56") (pintype "passive"))
    )
    (net (code "52") (name "/IN4-5") (class "Default")
      (node (ref "N4") (pin "6") (pinfunction "Cathode_\"5\"_6") (pintype "passive"))
      (node (ref "U11") (pin "58") (pinfunction "HVOUT47/18_58") (pintype "passive"))
    )
    (net (code "53") (name "/IN4-6") (class "Default")
      (node (ref "N4") (pin "7") (pinfunction "Cathode_\"6\"_7") (pintype "passive"))
      (node (ref "U11") (pin "59") (pinfunction "HVOUT46/19_59") (pintype "passive"))
    )
    (net (code "54") (name "/IN4-7") (class "Default")
      (node (ref "N4") (pin "8") (pinfunction "Cathode_\"7\"_8") (pintype "passive"))
      (node (ref "U11") (pin "60") (pinfunction "HVOUT45/20_60") (pintype "passive"))
    )
    (net (code "55") (name "/IN4-8") (class "Default")
      (node (ref "N4") (pin "10") (pinfunction "Cathode_\"8\"_10") (pintype "passive"))
      (node (ref "U11") (pin "62") (pinfunction "HVOUT43/22_62") (pintype "passive"))
    )
    (net (code "56") (name "/IN4-9") (class "Default")
      (node (ref "N4") (pin "11") (pinfunction "Cathode_\"9\"_11") (pintype "passive"))
      (node (ref "U11") (pin "63") (pinfunction "HVOUT42/23_63") (pintype "passive"))
    )
    (net (code "57") (name "/IO0") (class "Default")
      (node (ref "Q6") (pin "3") (pinfunction "C_3") (pintype "passive"))
      (node (ref "R20") (pin "2") (pinfunction "2_2") (pintype "passive"))
      (node (ref "U8") (pin "25") (pinfunction "IO0_25") (pintype "passive"))
    )
    (net (code "58") (name "/IR") (class "Default")
      (node (ref "IR") (pin "1") (pinfunction "OUT_1") (pintype "passive"))
      (node (ref "U8") (pin "37") (pinfunction "IO23_37") (pintype "passive"))
    )
    (net (code "59") (name "/LE_ESP") (class "Default")
      (node (ref "U6") (pin "5") (pinfunction "2A_5") (pintype "input"))
      (node (ref "U8") (pin "30") (pinfunction "IO18_30") (pintype "passive"))
    )
    (net (code "60") (name "/LE_HV") (class "Default")
      (node (ref "U11") (pin "29") (pinfunction "LE_29") (pintype "passive"))
      (node (ref "U6") (pin "6") (pinfunction "2Y_6") (pintype "output"))
    )
    (net (code "61") (name "/RADAR") (class "Default")
      (node (ref "JP3") (pin "3") (pinfunction "3_3") (pintype "passive"))
      (node (ref "U8") (pin "16") (pinfunction "IO13_16") (pintype "passive"))
    )
    (net (code "62") (name "/RGB") (class "Default")
      (node (ref "U12") (pin "4") (pinfunction "DIN_4") (pintype "passive"))
      (node (ref "U6") (pin "3") (pinfunction "1Y_3") (pintype "output"))
    )
    (net (code "63") (name "/RGB_ESP") (class "Default")
      (node (ref "U6") (pin "2") (pinfunction "1A_2") (pintype "input"))
      (node (ref "U8") (pin "12") (pinfunction "IO27_12") (pintype "passive"))
    )
    (net (code "64") (name "/RTS") (class "Default")
      (node (ref "JP1") (pin "5") (pinfunction "5_5") (pintype "passive"))
      (node (ref "Q5") (pin "2") (pinfunction "E_2") (pintype "passive"))
      (node (ref "R41") (pin "2") (pinfunction "2_2") (pintype "passive"))
    )
    (net (code "65") (name "/RX") (class "Default")
      (node (ref "JP1") (pin "2") (pinfunction "2_2") (pintype "passive"))
      (node (ref "U8") (pin "34") (pinfunction "RXD0_34") (pintype "passive"))
    )
    (net (code "66") (name "/SCL") (class "Default")
      (node (ref "R10") (pin "1") (pinfunction "1_1") (pintype "passive"))
      (node (ref "U4") (pin "4") (pinfunction "SCL_4") (pintype "passive"))
      (node (ref "U7") (pin "16") (pinfunction "SCL_16") (pintype "passive"))
      (node (ref "U8") (pin "33") (pinfunction "IO21_33") (pintype "passive"))
    )
    (net (code "67") (name "/SDA") (class "Default")
      (node (ref "R11") (pin "1") (pinfunction "1_1") (pintype "passive"))
      (node (ref "U4") (pin "1") (pinfunction "SDA_1") (pintype "passive"))
      (node (ref "U7") (pin "15") (pinfunction "SDA_15") (pintype "passive"))
      (node (ref "U8") (pin "36") (pinfunction "IO22_36") (pintype "passive"))
    )
    (net (code "68") (name "/SQW") (class "Default")
      (node (ref "U7") (pin "3") (pinfunction "~{INT}/SQW_3") (pintype "passive"))
      (node (ref "U8") (pin "27") (pinfunction "IO16_27") (pintype "passive"))
    )
    (net (code "69") (name "/TX") (class "Default")
      (node (ref "JP1") (pin "3") (pinfunction "3_3") (pintype "passive"))
      (node (ref "U8") (pin "35") (pinfunction "TXD0_35") (pintype "passive"))
    )
    (net (code "70") (name "/VBUS") (class "Default")
      (node (ref "RF1") (pin "1") (pinfunction "1_1") (pintype "passive"))
      (node (ref "USBC1") (pin "A4") (pinfunction "VBUS_A4") (pintype "passive"))
      (node (ref "USBC1") (pin "A9") (pinfunction "VBUS_A9") (pintype "passive"))
      (node (ref "USBC1") (pin "B4") (pinfunction "VBUS_B4") (pintype "passive"))
      (node (ref "USBC1") (pin "B9") (pinfunction "VBUS_B9") (pintype "passive"))
    )
    (net (code "71") (name "DGND") (class "Default")
      (node (ref "BT1") (pin "2") (pinfunction "-_2") (pintype "passive"))
      (node (ref "C10") (pin "2") (pinfunction "2_2") (pintype "passive"))
      (node (ref "C15") (pin "2") (pinfunction "2_2") (pintype "passive"))
      (node (ref "C16") (pin "2") (pinfunction "2_2") (pintype "passive"))
      (node (ref "C17") (pin "2") (pinfunction "2_2") (pintype "passive"))
      (node (ref "C18") (pin "2") (pinfunction "2_2") (pintype "passive"))
      (node (ref "C19") (pin "1") (pinfunction "1_1") (pintype "passive"))
      (node (ref "C2") (pin "2") (pinfunction "2_2") (pintype "passive"))
      (node (ref "C22") (pin "2") (pinfunction "2_2") (pintype "passive"))
      (node (ref "C23") (pin "2") (pinfunction "2_2") (pintype "passive"))
      (node (ref "C29") (pin "1") (pinfunction "1_1") (pintype "passive"))
      (node (ref "C3") (pin "1") (pinfunction "1_1") (pintype "passive"))
      (node (ref "C30") (pin "1") (pinfunction "1_1") (pintype "passive"))
      (node (ref "C31") (pin "1") (pinfunction "1_1") (pintype "passive"))
      (node (ref "C32") (pin "1") (pinfunction "1_1") (pintype "passive"))
      (node (ref "C33") (pin "2") (pinfunction "2_2") (pintype "passive"))
      (node (ref "C34") (pin "1") (pinfunction "1_1") (pintype "passive"))
      (node (ref "C4") (pin "1") (pinfunction "1_1") (pintype "passive"))
      (node (ref "C7") (pin "1") (pinfunction "1_1") (pintype "passive"))
      (node (ref "C9") (pin "2") (pinfunction "2_2") (pintype "passive"))
      (node (ref "D3") (pin "1") (pinfunction "A_1") (pintype "passive"))
      (node (ref "IR") (pin "2") (pinfunction "GND_2") (pintype "passive"))
      (node (ref "JP1") (pin "1") (pinfunction "1_1") (pintype "passive"))
      (node (ref "JP3") (pin "2") (pinfunction "2_2") (pintype "passive"))
      (node (ref "Q2") (pin "2") (pinfunction "E_2") (pintype "passive"))
      (node (ref "Q3") (pin "2") (pinfunction "E_2") (pintype "passive"))
      (node (ref "Q4") (pin "2") (pinfunction "E_2") (pintype "passive"))
      (node (ref "R21") (pin "1") (pinfunction "1_1") (pintype "passive"))
      (node (ref "R26") (pin "1") (pinfunction "1_1") (pintype "passive"))
      (node (ref "R3") (pin "1") (pinfunction "1_1") (pintype "passive"))
      (node (ref "R35") (pin "1") (pinfunction "1_1") (pintype "passive"))
      (node (ref "R36") (pin "1") (pinfunction "1_1") (pintype "passive"))
      (node (ref "R37") (pin "1") (pinfunction "1_1") (pintype "passive"))
      (node (ref "R42") (pin "1") (pinfunction "1_1") (pintype "passive"))
      (node (ref "R7") (pin "1") (pinfunction "1_1") (pintype "passive"))
      (node (ref "RST") (pin "1") (pinfunction "1_1") (pintype "passive"))
      (node (ref "T1") (pin "1") (pinfunction "1_1") (pintype "passive"))
      (node (ref "T2") (pin "1") (pinfunction "1_1") (pintype "passive"))
      (node (ref "T3") (pin "1") (pinfunction "1_1") (pintype "passive"))
      (node (ref "T4") (pin "1") (pinfunction "1_1") (pintype "passive"))
      (node (ref "U1") (pin "0") (pinfunction "GND_0") (pintype "passive"))
      (node (ref "U11") (pin "34") (pinfunction "GND_34") (pintype "passive"))
      (node (ref "U11") (pin "35") (pinfunction "POL_35") (pintype "passive"))
      (node (ref "U12") (pin "3") (pinfunction "VSS_3") (pintype "passive"))
      (node (ref "U13") (pin "3") (pinfunction "VSS_3") (pintype "passive"))
      (node (ref "U14") (pin "3") (pinfunction "VSS_3") (pintype "passive"))
      (node (ref "U15") (pin "3") (pinfunction "VSS_3") (pintype "passive"))
      (node (ref "U3") (pin "2") (pinfunction "GND_2") (pintype "passive"))
      (node (ref "U4") (pin "0") (pinfunction "die_pad_0") (pintype "passive"))
      (node (ref "U4") (pin "7") (pinfunction "R_7") (pintype "passive"))
      (node (ref "U4") (pin "8") (pinfunction "VSS_8") (pintype "passive"))
      (node (ref "U5") (pin "1") (pinfunction "GND_1") (pintype "passive"))
      (node (ref "U6") (pin "1") (pinfunction "1~{OE}_1") (pintype "passive"))
      (node (ref "U6") (pin "10") (pinfunction "3~{OE}_10") (pintype "passive"))
      (node (ref "U6") (pin "13") (pinfunction "4~{OE}_13") (pintype "passive"))
      (node (ref "U6") (pin "4") (pinfunction "2~{OE}_4") (pintype "passive"))
      (node (ref "U6") (pin "7") (pinfunction "GND_7") (pintype "passive"))
      (node (ref "U7") (pin "10") (pinfunction "NC_10") (pintype "passive"))
      (node (ref "U7") (pin "11") (pinfunction "NC_11") (pintype "passive"))
      (node (ref "U7") (pin "12") (pinfunction "NC_12") (pintype "passive"))
      (node (ref "U7") (pin "13") (pinfunction "GND_13") (pintype "passive"))
      (node (ref "U7") (pin "5") (pinfunction "NC_5") (pintype "passive"))
      (node (ref "U7") (pin "6") (pinfunction "NC_6") (pintype "passive"))
      (node (ref "U7") (pin "7") (pinfunction "NC_7") (pintype "passive"))
      (node (ref "U7") (pin "8") (pinfunction "NC_8") (pintype "passive"))
      (node (ref "U7") (pin "9") (pinfunction "NC_9") (pintype "passive"))
      (node (ref "U8") (pin "1") (pinfunction "GND_1") (pintype "passive"))
      (node (ref "U8") (pin "15") (pinfunction "GND_15") (pintype "passive"))
      (node (ref "U8") (pin "38") (pinfunction "GND_38") (pintype "passive"))
      (node (ref "U8") (pin "39") (pinfunction "GND_39") (pintype "passive"))
      (node (ref "USBC1") (pin "0") (pinfunction "0_0") (pintype "passive"))
      (node (ref "USBC1") (pin "A1") (pinfunction "GND_A1") (pintype "passive"))
      (node (ref "USBC1") (pin "A12") (pinfunction "GND_A12") (pintype "passive"))
      (node (ref "USBC1") (pin "B1") (pinfunction "GND_B1") (pintype "passive"))
      (node (ref "USBC1") (pin "B12") (pinfunction "GND_B12") (pintype "passive"))
    )
    (net (code "72") (name "GND") (class "Default")
      (node (ref "C12") (pin "1") (pinfunction "1_1") (pintype "passive"))
      (node (ref "C13") (pin "1") (pinfunction "1_1") (pintype "passive"))
      (node (ref "C20") (pin "2") (pinfunction "2_2") (pintype "passive"))
      (node (ref "C21") (pin "2") (pinfunction "2_2") (pintype "passive"))
      (node (ref "C24") (pin "1") (pinfunction "1_1") (pintype "passive"))
      (node (ref "C26") (pin "1") (pinfunction "1_1") (pintype "passive"))
      (node (ref "C27") (pin "2") (pinfunction "2_2") (pintype "passive"))
      (node (ref "C35") (pin "1") (pinfunction "1_1") (pintype "passive"))
      (node (ref "C5") (pin "1") (pinfunction "1_1") (pintype "passive"))
      (node (ref "C6") (pin "1") (pinfunction "1_1") (pintype "passive"))
      (node (ref "C8") (pin "1") (pinfunction "1_1") (pintype "passive"))
      (node (ref "D1") (pin "1") (pinfunction "A_1") (pintype "passive"))
      (node (ref "R15") (pin "1") (pinfunction "1_1") (pintype "passive"))
      (node (ref "R17") (pin "1") (pinfunction "1_1") (pintype "passive"))
      (node (ref "R18") (pin "2") (pinfunction "2_2") (pintype "passive"))
      (node (ref "R37") (pin "2") (pinfunction "2_2") (pintype "passive"))
      (node (ref "R5") (pin "1") (pinfunction "1_1") (pintype "passive"))
      (node (ref "R8") (pin "1") (pinfunction "1_1") (pintype "passive"))
      (node (ref "R9") (pin "1") (pinfunction "1_1") (pintype "passive"))
      (node (ref "U2") (pin "4") (pinfunction "GND_4") (pintype "passive"))
      (node (ref "U9") (pin "6") (pinfunction "GND_6") (pintype "passive"))
      (node (ref "U9") (pin "7") (pinfunction "GND_7") (pintype "passive"))
    )
    (net (code "73") (name "Net-(BT1-+)") (class "Default")
      (node (ref "BT1") (pin "1") (pinfunction "+_1") (pintype "passive"))
      (node (ref "U7") (pin "14") (pinfunction "VBAT_14") (pintype "passive"))
    )
    (net (code "74") (name "Net-(C14-Pad1)") (class "Default")
      (node (ref "C14") (pin "1") (pinfunction "1_1") (pintype "passive"))
      (node (ref "R9") (pin "2") (pinfunction "2_2") (pintype "passive"))
    )
    (net (code "75") (name "Net-(D1-K)") (class "Default")
      (node (ref "C1") (pin "1") (pinfunction "1_1") (pintype "passive"))
      (node (ref "D1") (pin "2") (pinfunction "K_2") (pintype "passive"))
      (node (ref "L1") (pin "1") (pinfunction "1_1") (pintype "passive"))
      (node (ref "U2") (pin "3") (pinfunction "SW_3") (pintype "passive"))
    )
    (net (code "76") (name "Net-(D2-A)") (class "Default")
      (node (ref "D2") (pin "1") (pinfunction "A_1") (pintype "passive"))
      (node (ref "L2") (pin "2") (pinfunction "2_2") (pintype "passive"))
      (node (ref "Q1") (pin "2") (pinfunction "D_2") (pintype "passive"))
    )
    (net (code "77") (name "Net-(D3-K)") (class "Default")
      (node (ref "D3") (pin "2") (pinfunction "K_2") (pintype "passive"))
      (node (ref "R24") (pin "1") (pinfunction "1_1") (pintype "passive"))
      (node (ref "U11") (pin "40") (pinfunction "VPP_40") (pintype "passive"))
    )
    (net (code "78") (name "Net-(IR-VCC)") (class "Default")
      (node (ref "C22") (pin "1") (pinfunction "1_1") (pintype "passive"))
      (node (ref "C23") (pin "1") (pinfunction "1_1") (pintype "passive"))
      (node (ref "IR") (pin "3") (pinfunction "VCC_3") (pintype "passive"))
      (node (ref "R19") (pin "1") (pinfunction "1_1") (pintype "passive"))
    )
    (net (code "79") (name "Net-(JP2-Pad2)") (class "Default")
      (node (ref "JP2") (pin "2") (pinfunction "2_2") (pintype "passive"))
      (node (ref "R22") (pin "1") (pinfunction "1_1") (pintype "passive"))
    )
    (net (code "80") (name "Net-(JP2-Pad4)") (class "Default")
      (node (ref "JP2") (pin "4") (pinfunction "4_4") (pintype "passive"))
      (node (ref "R23") (pin "1") (pinfunction "1_1") (pintype "passive"))
    )
    (net (code "81") (name "Net-(N1-Anode)") (class "Default")
      (node (ref "N1") (pin "13") (pinfunction "Anode_13") (pintype "passive"))
      (node (ref "R27") (pin "2") (pinfunction "2_2") (pintype "passive"))
    )
    (net (code "82") (name "Net-(N2-Anode)") (class "Default")
      (node (ref "N2") (pin "13") (pinfunction "Anode_13") (pintype "passive"))
      (node (ref "R28") (pin "2") (pinfunction "2_2") (pintype "passive"))
    )
    (net (code "83") (name "Net-(N2-Cathode_comma)") (class "Default")
      (node (ref "N2") (pin "9") (pinfunction "Cathode_comma_9") (pintype "passive"))
      (node (ref "R32") (pin "2") (pinfunction "2_2") (pintype "passive"))
    )
    (net (code "84") (name "Net-(N3-Anode)") (class "Default")
      (node (ref "N3") (pin "13") (pinfunction "Anode_13") (pintype "passive"))
      (node (ref "R29") (pin "2") (pinfunction "2_2") (pintype "passive"))
    )
    (net (code "85") (name "Net-(N3-Cathode_comma)") (class "Default")
      (node (ref "N3") (pin "9") (pinfunction "Cathode_comma_9") (pintype "passive"))
      (node (ref "R31") (pin "2") (pinfunction "2_2") (pintype "passive"))
    )
    (net (code "86") (name "Net-(N4-Anode)") (class "Default")
      (node (ref "N4") (pin "13") (pinfunction "Anode_13") (pintype "passive"))
      (node (ref "R30") (pin "2") (pinfunction "2_2") (pintype "passive"))
    )
    (net (code "87") (name "Net-(Q1-G)") (class "Default")
      (node (ref "Q1") (pin "1") (pinfunction "G_1") (pintype "passive"))
      (node (ref "U9") (pin "1") (pinfunction "EXT_1") (pintype "passive"))
    )
    (net (code "88") (name "Net-(Q1-S)") (class "Default")
      (node (ref "Q1") (pin "3") (pinfunction "S_3") (pintype "passive"))
      (node (ref "R18") (pin "1") (pinfunction "1_1") (pintype "passive"))
      (node (ref "U9") (pin "8") (pinfunction "CS_8") (pintype "passive"))
    )
    (net (code "89") (name "Net-(Q2-B)") (class "Default")
      (node (ref "Q2") (pin "1") (pinfunction "B_1") (pintype "passive"))
      (node (ref "R25") (pin "1") (pinfunction "1_1") (pintype "passive"))
      (node (ref "R26") (pin "2") (pinfunction "2_2") (pintype "passive"))
    )
    (net (code "90") (name "Net-(Q2-C)") (class "Default")
      (node (ref "JP2") (pin "1") (pinfunction "1_1") (pintype "passive"))
      (node (ref "JP2") (pin "3") (pinfunction "3_3") (pintype "passive"))
      (node (ref "Q2") (pin "3") (pinfunction "C_3") (pintype "passive"))
    )
    (net (code "91") (name "Net-(Q3-B)") (class "Default")
      (node (ref "Q3") (pin "1") (pinfunction "B_1") (pintype "passive"))
      (node (ref "R33") (pin "1") (pinfunction "1_1") (pintype "passive"))
      (node (ref "R35") (pin "2") (pinfunction "2_2") (pintype "passive"))
    )
    (net (code "92") (name "Net-(Q3-C)") (class "Default")
      (node (ref "Q3") (pin "3") (pinfunction "C_3") (pintype "passive"))
      (node (ref "R31") (pin "1") (pinfunction "1_1") (pintype "passive"))
    )
    (net (code "93") (name "Net-(Q4-B)") (class "Default")
      (node (ref "Q4") (pin "1") (pinfunction "B_1") (pintype "passive"))
      (node (ref "R34") (pin "1") (pinfunction "1_1") (pintype "passive"))
      (node (ref "R36") (pin "2") (pinfunction "2_2") (pintype "passive"))
    )
    (net (code "94") (name "Net-(Q4-C)") (class "Default")
      (node (ref "Q4") (pin "3") (pinfunction "C_3") (pintype "passive"))
      (node (ref "R32") (pin "1") (pinfunction "1_1") (pintype "passive"))
    )
    (net (code "95") (name "Net-(Q5-B)") (class "Default")
      (node (ref "Q5") (pin "1") (pinfunction "B_1") (pintype "passive"))
      (node (ref "R40") (pin "1") (pinfunction "1_1") (pintype "passive"))
    )
    (net (code "96") (name "Net-(Q6-B)") (class "Default")
      (node (ref "Q6") (pin "1") (pinfunction "B_1") (pintype "passive"))
      (node (ref "R41") (pin "1") (pinfunction "1_1") (pintype "passive"))
    )
    (net (code "97") (name "Net-(U1-CFG1)") (class "Default")
      (node (ref "R3") (pin "2") (pinfunction "2_2") (pintype "passive"))
      (node (ref "U1") (pin "9") (pinfunction "CFG1_9") (pintype "passive"))
    )
    (net (code "98") (name "Net-(U1-VBUS)") (class "Default")
      (node (ref "R4") (pin "2") (pinfunction "2_2") (pintype "passive"))
      (node (ref "U1") (pin "8") (pinfunction "VBUS_8") (pintype "passive"))
    )
    (net (code "99") (name "Net-(U1-VDD)") (class "Default")
      (node (ref "C2") (pin "1") (pinfunction "1_1") (pintype "passive"))
      (node (ref "R2") (pin "1") (pinfunction "1_1") (pintype "passive"))
      (node (ref "U1") (pin "1") (pinfunction "VDD_1") (pintype "passive"))
    )
    (net (code "100") (name "Net-(U2-BS)") (class "Default")
      (node (ref "C1") (pin "2") (pinfunction "2_2") (pintype "passive"))
      (node (ref "U2") (pin "1") (pinfunction "BS_1") (pintype "passive"))
    )
    (net (code "101") (name "Net-(U2-COMP)") (class "Default")
      (node (ref "C14") (pin "2") (pinfunction "2_2") (pintype "passive"))
      (node (ref "U2") (pin "6") (pinfunction "COMP_6") (pintype "passive"))
    )
    (net (code "102") (name "Net-(U2-EN)") (class "Default")
      (node (ref "R1") (pin "1") (pinfunction "1_1") (pintype "passive"))
      (node (ref "R5") (pin "2") (pinfunction "2_2") (pintype "passive"))
      (node (ref "U2") (pin "7") (pinfunction "EN_7") (pintype "passive"))
    )
    (net (code "103") (name "Net-(U2-FB)") (class "Default")
      (node (ref "R6") (pin "2") (pinfunction "2_2") (pintype "passive"))
      (node (ref "R8") (pin "2") (pinfunction "2_2") (pintype "passive"))
      (node (ref "U2") (pin "5") (pinfunction "FB_5") (pintype "passive"))
    )
    (net (code "104") (name "Net-(U2-SS)") (class "Default")
      (node (ref "C8") (pin "2") (pinfunction "2_2") (pintype "passive"))
      (node (ref "U2") (pin "8") (pinfunction "SS_8") (pintype "passive"))
    )
    (net (code "105") (name "Net-(U4-ADDR)") (class "Default")
      (node (ref "R7") (pin "2") (pinfunction "2_2") (pintype "passive"))
      (node (ref "U4") (pin "2") (pinfunction "ADDR_2") (pintype "passive"))
    )
    (net (code "106") (name "Net-(U8-IO2)") (class "Default")
      (node (ref "R21") (pin "2") (pinfunction "2_2") (pintype "passive"))
      (node (ref "U8") (pin "24") (pinfunction "IO2_24") (pintype "passive"))
    )
    (net (code "107") (name "Net-(U8-IO17)") (class "Default")
      (node (ref "R39") (pin "2") (pinfunction "2_2") (pintype "passive"))
      (node (ref "U8") (pin "28") (pinfunction "IO17_28") (pintype "passive"))
    )
    (net (code "108") (name "Net-(U8-IO19)") (class "Default")
      (node (ref "R38") (pin "2") (pinfunction "2_2") (pintype "passive"))
      (node (ref "U8") (pin "31") (pinfunction "IO19_31") (pintype "passive"))
    )
    (net (code "109") (name "Net-(U9-FB)") (class "Default")
      (node (ref "C26") (pin "2") (pinfunction "2_2") (pintype "passive"))
      (node (ref "R14") (pin "2") (pinfunction "2_2") (pintype "passive"))
      (node (ref "R17") (pin "2") (pinfunction "2_2") (pintype "passive"))
      (node (ref "U9") (pin "3") (pinfunction "FB_3") (pintype "passive"))
    )
    (net (code "110") (name "Net-(U9-REF)") (class "Default")
      (node (ref "C27") (pin "1") (pinfunction "1_1") (pintype "passive"))
      (node (ref "U9") (pin "5") (pinfunction "REF_5") (pintype "passive"))
    )
    (net (code "111") (name "Net-(U12-DOUT)") (class "Default")
      (node (ref "U12") (pin "2") (pinfunction "DOUT_2") (pintype "passive"))
      (node (ref "U13") (pin "4") (pinfunction "DIN_4") (pintype "passive"))
    )
    (net (code "112") (name "Net-(U13-DOUT)") (class "Default")
      (node (ref "U13") (pin "2") (pinfunction "DOUT_2") (pintype "passive"))
      (node (ref "U14") (pin "4") (pinfunction "DIN_4") (pintype "passive"))
    )
    (net (code "113") (name "Net-(U14-DOUT)") (class "Default")
      (node (ref "U14") (pin "2") (pinfunction "DOUT_2") (pintype "passive"))
      (node (ref "U15") (pin "4") (pinfunction "DIN_4") (pintype "passive"))
    )
    (net (code "114") (name "V3.3") (class "Default")
      (node (ref "C10") (pin "1") (pinfunction "1_1") (pintype "passive"))
      (node (ref "C15") (pin "1") (pinfunction "1_1") (pintype "passive"))
      (node (ref "C16") (pin "1") (pinfunction "1_1") (pintype "passive"))
      (node (ref "C17") (pin "1") (pinfunction "1_1") (pintype "passive"))
      (node (ref "C3") (pin "2") (pinfunction "2_2") (pintype "passive"))
      (node (ref "C4") (pin "2") (pinfunction "2_2") (pintype "passive"))
      (node (ref "C7") (pin "2") (pinfunction "2_2") (pintype "passive"))
      (node (ref "R10") (pin "2") (pinfunction "2_2") (pintype "passive"))
      (node (ref "R11") (pin "2") (pinfunction "2_2") (pintype "passive"))
      (node (ref "R13") (pin "2") (pinfunction "2_2") (pintype "passive"))
      (node (ref "R19") (pin "2") (pinfunction "2_2") (pintype "passive"))
      (node (ref "R20") (pin "1") (pinfunction "1_1") (pintype "passive"))
      (node (ref "U3") (pin "5") (pinfunction "VCC_5") (pintype "passive"))
      (node (ref "U4") (pin "5") (pinfunction "VDD_5") (pintype "passive"))
      (node (ref "U4") (pin "6") (pinfunction "nRESET_6") (pintype "passive"))
      (node (ref "U5") (pin "2") (pinfunction "Vout_2") (pintype "passive"))
      (node (ref "U7") (pin "2") (pinfunction "VCC_2") (pintype "passive"))
      (node (ref "U8") (pin "2") (pinfunction "3V3_2") (pintype "passive"))
    )
    (net (code "115") (name "V5") (class "Default")
      (node (ref "C12") (pin "2") (pinfunction "2_2") (pintype "passive"))
      (node (ref "C13") (pin "2") (pinfunction "2_2") (pintype "passive"))
      (node (ref "C18") (pin "1") (pinfunction "1_1") (pintype "passive"))
      (node (ref "C29") (pin "2") (pinfunction "2_2") (pintype "passive"))
      (node (ref "C30") (pin "2") (pinfunction "2_2") (pintype "passive"))
      (node (ref "C31") (pin "2") (pinfunction "2_2") (pintype "passive"))
      (node (ref "C32") (pin "2") (pinfunction "2_2") (pintype "passive"))
      (node (ref "C33") (pin "1") (pinfunction "1_1") (pintype "passive"))
      (node (ref "C34") (pin "2") (pinfunction "2_2") (pintype "passive"))
      (node (ref "C9") (pin "1") (pinfunction "1_1") (pintype "passive"))
      (node (ref "JP3") (pin "1") (pinfunction "1_1") (pintype "passive"))
      (node (ref "L1") (pin "2") (pinfunction "2_2") (pintype "passive"))
      (node (ref "R42") (pin "2") (pinfunction "2_2") (pintype "passive"))
      (node (ref "R6") (pin "1") (pinfunction "1_1") (pintype "passive"))
      (node (ref "U11") (pin "31") (pinfunction "BL_31") (pintype "passive"))
      (node (ref "U11") (pin "32") (pinfunction "VDD_32") (pintype "passive"))
      (node (ref "U11") (pin "33") (pinfunction "DIR_33") (pintype "passive"))
      (node (ref "U12") (pin "1") (pinfunction "VDD_1") (pintype "passive"))
      (node (ref "U13") (pin "1") (pinfunction "VDD_1") (pintype "passive"))
      (node (ref "U14") (pin "1") (pinfunction "VDD_1") (pintype "passive"))
      (node (ref "U15") (pin "1") (pinfunction "VDD_1") (pintype "passive"))
      (node (ref "U5") (pin "3") (pinfunction "Vin_3") (pintype "passive"))
      (node (ref "U6") (pin "14") (pinfunction "VCC_14") (pintype "passive"))
    )
    (net (code "116") (name "V12") (class "Default")
      (node (ref "C21") (pin "1") (pinfunction "1_1") (pintype "passive"))
      (node (ref "C24") (pin "2") (pinfunction "2_2") (pintype "passive"))
      (node (ref "C5") (pin "2") (pinfunction "2_2") (pintype "passive"))
      (node (ref "C6") (pin "2") (pinfunction "2_2") (pintype "passive"))
      (node (ref "L2") (pin "1") (pinfunction "1_1") (pintype "passive"))
      (node (ref "R1") (pin "2") (pinfunction "2_2") (pintype "passive"))
      (node (ref "R2") (pin "2") (pinfunction "2_2") (pintype "passive"))
      (node (ref "R4") (pin "1") (pinfunction "1_1") (pintype "passive"))
      (node (ref "RF1") (pin "2") (pinfunction "2_2") (pintype "passive"))
      (node (ref "U2") (pin "2") (pinfunction "VIN_2") (pintype "passive"))
      (node (ref "U9") (pin "2") (pinfunction "VIN_2") (pintype "passive"))
    )
    (net (code "117") (name "VH") (class "Default")
      (node (ref "C20") (pin "1") (pinfunction "1_1") (pintype "passive"))
      (node (ref "C35") (pin "2") (pinfunction "2_2") (pintype "passive"))
      (node (ref "D2") (pin "2") (pinfunction "K_2") (pintype "passive"))
      (node (ref "R14") (pin "1") (pinfunction "1_1") (pintype "passive"))
      (node (ref "R15") (pin "2") (pinfunction "2_2") (pintype "passive"))
      (node (ref "R22") (pin "2") (pinfunction "2_2") (pintype "passive"))
      (node (ref "R23") (pin "2") (pinfunction "2_2") (pintype "passive"))
      (node (ref "R24") (pin "2") (pinfunction "2_2") (pintype "passive"))
      (node (ref "R27") (pin "1") (pinfunction "1_1") (pintype "passive"))
      (node (ref "R28") (pin "1") (pinfunction "1_1") (pintype "passive"))
      (node (ref "R29") (pin "1") (pinfunction "1_1") (pintype "passive"))
      (node (ref "R30") (pin "1") (pinfunction "1_1") (pintype "passive"))
    )
    (net (code "118") (name "unconnected-(N1-Cathode_comma-Pad9)") (class "Default")
      (node (ref "N1") (pin "9") (pinfunction "Cathode_comma_9") (pintype "passive+no_connect"))
    )
    (net (code "119") (name "unconnected-(N4-Cathode_comma-Pad9)") (class "Default")
      (node (ref "N4") (pin "9") (pinfunction "Cathode_comma_9") (pintype "passive+no_connect"))
    )
    (net (code "120") (name "unconnected-(U1-CFG2-Pad2)") (class "Default")
      (node (ref "U1") (pin "2") (pinfunction "CFG2_2") (pintype "passive+no_connect"))
    )
    (net (code "121") (name "unconnected-(U1-CFG3-Pad3)") (class "Default")
      (node (ref "U1") (pin "3") (pinfunction "CFG3_3") (pintype "passive+no_connect"))
    )
    (net (code "122") (name "unconnected-(U1-PG-Pad10)") (class "Default")
      (node (ref "U1") (pin "10") (pinfunction "PG_10") (pintype "passive+no_connect"))
    )
    (net (code "123") (name "unconnected-(U2-GND-Pad9)") (class "Default")
      (node (ref "U2") (pin "9") (pinfunction "GND_9") (pintype "passive"))
    )
    (net (code "124") (name "unconnected-(U4-ALERT-Pad3)") (class "Default")
      (node (ref "U4") (pin "3") (pinfunction "ALERT_3") (pintype "passive+no_connect"))
    )
    (net (code "125") (name "unconnected-(U7-32kHz-Pad1)") (class "Default")
      (node (ref "U7") (pin "1") (pinfunction "32kHz_1") (pintype "passive+no_connect"))
    )
    (net (code "126") (name "unconnected-(U7-~{RST}-Pad4)") (class "Default")
      (node (ref "U7") (pin "4") (pinfunction "~{RST}_4") (pintype "passive+no_connect"))
    )
    (net (code "127") (name "unconnected-(U8-CLK-Pad20)") (class "Default")
      (node (ref "U8") (pin "20") (pinfunction "CLK_20") (pintype "passive"))
    )
    (net (code "128") (name "unconnected-(U8-CMD-Pad19)") (class "Default")
      (node (ref "U8") (pin "19") (pinfunction "CMD_19") (pintype "passive"))
    )
    (net (code "129") (name "unconnected-(U8-IO4-Pad26)") (class "Default")
      (node (ref "U8") (pin "26") (pinfunction "IO4_26") (pintype "passive"))
    )
    (net (code "130") (name "unconnected-(U8-IO5-Pad29)") (class "Default")
      (node (ref "U8") (pin "29") (pinfunction "IO5_29") (pintype "passive"))
    )
    (net (code "131") (name "unconnected-(U8-IO12-Pad14)") (class "Default")
      (node (ref "U8") (pin "14") (pinfunction "IO12_14") (pintype "passive"))
    )
    (net (code "132") (name "unconnected-(U8-IO15-Pad23)") (class "Default")
      (node (ref "U8") (pin "23") (pinfunction "IO15_23") (pintype "passive"))
    )
    (net (code "133") (name "unconnected-(U8-IO32-Pad8)") (class "Default")
      (node (ref "U8") (pin "8") (pinfunction "IO32_8") (pintype "passive"))
    )
    (net (code "134") (name "unconnected-(U8-IO34-Pad6)") (class "Default")
      (node (ref "U8") (pin "6") (pinfunction "IO34_6") (pintype "passive"))
    )
    (net (code "135") (name "unconnected-(U8-IO35-Pad7)") (class "Default")
      (node (ref "U8") (pin "7") (pinfunction "IO35_7") (pintype "passive"))
    )
    (net (code "136") (name "unconnected-(U8-NC-Pad32)") (class "Default")
      (node (ref "U8") (pin "32") (pinfunction "NC_32") (pintype "passive"))
    )
    (net (code "137") (name "unconnected-(U8-SD0-Pad21)") (class "Default")
      (node (ref "U8") (pin "21") (pinfunction "SD0_21") (pintype "passive"))
    )
    (net (code "138") (name "unconnected-(U8-SD1-Pad22)") (class "Default")
      (node (ref "U8") (pin "22") (pinfunction "SD1_22") (pintype "passive"))
    )
    (net (code "139") (name "unconnected-(U8-SD2-Pad17)") (class "Default")
      (node (ref "U8") (pin "17") (pinfunction "SD2_17") (pintype "passive"))
    )
    (net (code "140") (name "unconnected-(U8-SD3-Pad18)") (class "Default")
      (node (ref "U8") (pin "18") (pinfunction "SD3_18") (pintype "passive"))
    )
    (net (code "141") (name "unconnected-(U8-SENSOR_VN-Pad5)") (class "Default")
      (node (ref "U8") (pin "5") (pinfunction "SENSOR_VN_5") (pintype "passive"))
    )
    (net (code "142") (name "unconnected-(U8-SENSOR_VP-Pad4)") (class "Default")
      (node (ref "U8") (pin "4") (pinfunction "SENSOR_VP_4") (pintype "passive"))
    )
    (net (code "143") (name "unconnected-(U11-DIN4{slash}DOUT1(A)-Pad28)") (class "Default")
      (node (ref "U11") (pin "28") (pinfunction "DIN4/DOUT1(A)_28") (pintype "passive+no_connect"))
    )
    (net (code "144") (name "unconnected-(U11-DOUT3{slash}DIN2(B)-Pad37)") (class "Default")
      (node (ref "U11") (pin "37") (pinfunction "DOUT3/DIN2(B)_37") (pintype "passive+no_connect"))
    )
    (net (code "145") (name "unconnected-(U11-DOUT4{slash}DIN1(B)-Pad36)") (class "Default")
      (node (ref "U11") (pin "36") (pinfunction "DOUT4/DIN1(B)_36") (pintype "passive+no_connect"))
    )
    (net (code "146") (name "unconnected-(U11-HVOUT4{slash}61-Pad21)") (class "Default")
      (node (ref "U11") (pin "21") (pinfunction "HVOUT4/61_21") (pintype "passive+no_connect"))
    )
    (net (code "147") (name "unconnected-(U11-HVOUT8{slash}57-Pad17)") (class "Default")
      (node (ref "U11") (pin "17") (pinfunction "HVOUT8/57_17") (pintype "passive+no_connect"))
    )
    (net (code "148") (name "unconnected-(U11-HVOUT12{slash}53-Pad13)") (class "Default")
      (node (ref "U11") (pin "13") (pinfunction "HVOUT12/53_13") (pintype "passive+no_connect"))
    )
    (net (code "149") (name "unconnected-(U11-HVOUT16{slash}49-Pad9)") (class "Default")
      (node (ref "U11") (pin "9") (pinfunction "HVOUT16/49_9") (pintype "passive+no_connect"))
    )
    (net (code "150") (name "unconnected-(U11-HVOUT20{slash}45-Pad5)") (class "Default")
      (node (ref "U11") (pin "5") (pinfunction "HVOUT20/45_5") (pintype "passive+no_connect"))
    )
    (net (code "151") (name "unconnected-(U11-HVOUT24{slash}41-Pad1)") (class "Default")
      (node (ref "U11") (pin "1") (pinfunction "HVOUT24/41_1") (pintype "passive+no_connect"))
    )
    (net (code "152") (name "unconnected-(U11-HVOUT28{slash}37-Pad77)") (class "Default")
      (node (ref "U11") (pin "77") (pinfunction "HVOUT28/37_77") (pintype "passive+no_connect"))
    )
    (net (code "153") (name "unconnected-(U11-HVOUT32{slash}33-Pad73)") (class "Default")
      (node (ref "U11") (pin "73") (pinfunction "HVOUT32/33_73") (pintype "passive+no_connect"))
    )
    (net (code "154") (name "unconnected-(U11-HVOUT36{slash}29-Pad69)") (class "Default")
      (node (ref "U11") (pin "69") (pinfunction "HVOUT36/29_69") (pintype "passive+no_connect"))
    )
    (net (code "155") (name "unconnected-(U11-HVOUT40{slash}25-Pad65)") (class "Default")
      (node (ref "U11") (pin "65") (pinfunction "HVOUT40/25_65") (pintype "passive+no_connect"))
    )
    (net (code "156") (name "unconnected-(U11-HVOUT44{slash}21-Pad61)") (class "Default")
      (node (ref "U11") (pin "61") (pinfunction "HVOUT44/21_61") (pintype "passive+no_connect"))
    )
    (net (code "157") (name "unconnected-(U11-HVOUT48{slash}17-Pad57)") (class "Default")
      (node (ref "U11") (pin "57") (pinfunction "HVOUT48/17_57") (pintype "passive+no_connect"))
    )
    (net (code "158") (name "unconnected-(U11-HVOUT52{slash}13-Pad53)") (class "Default")
      (node (ref "U11") (pin "53") (pinfunction "HVOUT52/13_53") (pintype "passive+no_connect"))
    )
    (net (code "159") (name "unconnected-(U11-HVOUT54{slash}11-Pad51)") (class "Default")
      (node (ref "U11") (pin "51") (pinfunction "HVOUT54/11_51") (pintype "passive+no_connect"))
    )
    (net (code "160") (name "unconnected-(U11-HVOUT55{slash}10-Pad50)") (class "Default")
      (node (ref "U11") (pin "50") (pinfunction "HVOUT55/10_50") (pintype "passive+no_connect"))
    )
    (net (code "161") (name "unconnected-(U11-HVOUT56{slash}9-Pad49)") (class "Default")
      (node (ref "U11") (pin "49") (pinfunction "HVOUT56/9_49") (pintype "passive+no_connect"))
    )
    (net (code "162") (name "unconnected-(U11-HVOUT57{slash}8-Pad48)") (class "Default")
      (node (ref "U11") (pin "48") (pinfunction "HVOUT57/8_48") (pintype "passive+no_connect"))
    )
    (net (code "163") (name "unconnected-(U11-HVOUT58{slash}7-Pad47)") (class "Default")
      (node (ref "U11") (pin "47") (pinfunction "HVOUT58/7_47") (pintype "passive+no_connect"))
    )
    (net (code "164") (name "unconnected-(U11-HVOUT59{slash}6-Pad46)") (class "Default")
      (node (ref "U11") (pin "46") (pinfunction "HVOUT59/6_46") (pintype "passive+no_connect"))
    )
    (net (code "165") (name "unconnected-(U11-HVOUT60{slash}5-Pad45)") (class "Default")
      (node (ref "U11") (pin "45") (pinfunction "HVOUT60/5_45") (pintype "passive+no_connect"))
    )
    (net (code "166") (name "unconnected-(U11-HVOUT61{slash}4-Pad44)") (class "Default")
      (node (ref "U11") (pin "44") (pinfunction "HVOUT61/4_44") (pintype "passive+no_connect"))
    )
    (net (code "167") (name "unconnected-(U11-HVOUT62{slash}3-Pad43)") (class "Default")
      (node (ref "U11") (pin "43") (pinfunction "HVOUT62/3_43") (pintype "passive+no_connect"))
    )
    (net (code "168") (name "unconnected-(U11-HVOUT63{slash}2-Pad42)") (class "Default")
      (node (ref "U11") (pin "42") (pinfunction "HVOUT63/2_42") (pintype "passive+no_connect"))
    )
    (net (code "169") (name "unconnected-(U11-HVOUT64{slash}1-Pad41)") (class "Default")
      (node (ref "U11") (pin "41") (pinfunction "HVOUT64/1_41") (pintype "passive+no_connect"))
    )
    (net (code "170") (name "unconnected-(U15-DOUT-Pad2)") (class "Default")
      (node (ref "U15") (pin "2") (pinfunction "DOUT_2") (pintype "passive+no_connect"))
    )
    (net (code "171") (name "unconnected-(USBC1-SBU1-PadA8)") (class "Default")
      (node (ref "USBC1") (pin "A8") (pinfunction "SBU1_A8") (pintype "passive+no_connect"))
    )
    (net (code "172") (name "unconnected-(USBC1-SBU2-PadB8)") (class "Default")
      (node (ref "USBC1") (pin "B8") (pinfunction "SBU2_B8") (pintype "passive+no_connect"))
    )
  )
)
